# Battery_Monitoring_V3.net
KiCad netlist of a schematic drawn in EAGLE
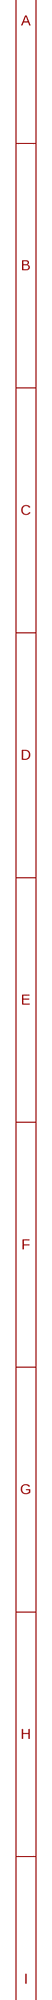
[diagram p0: schematic, sheet 1, part 1 of 2]
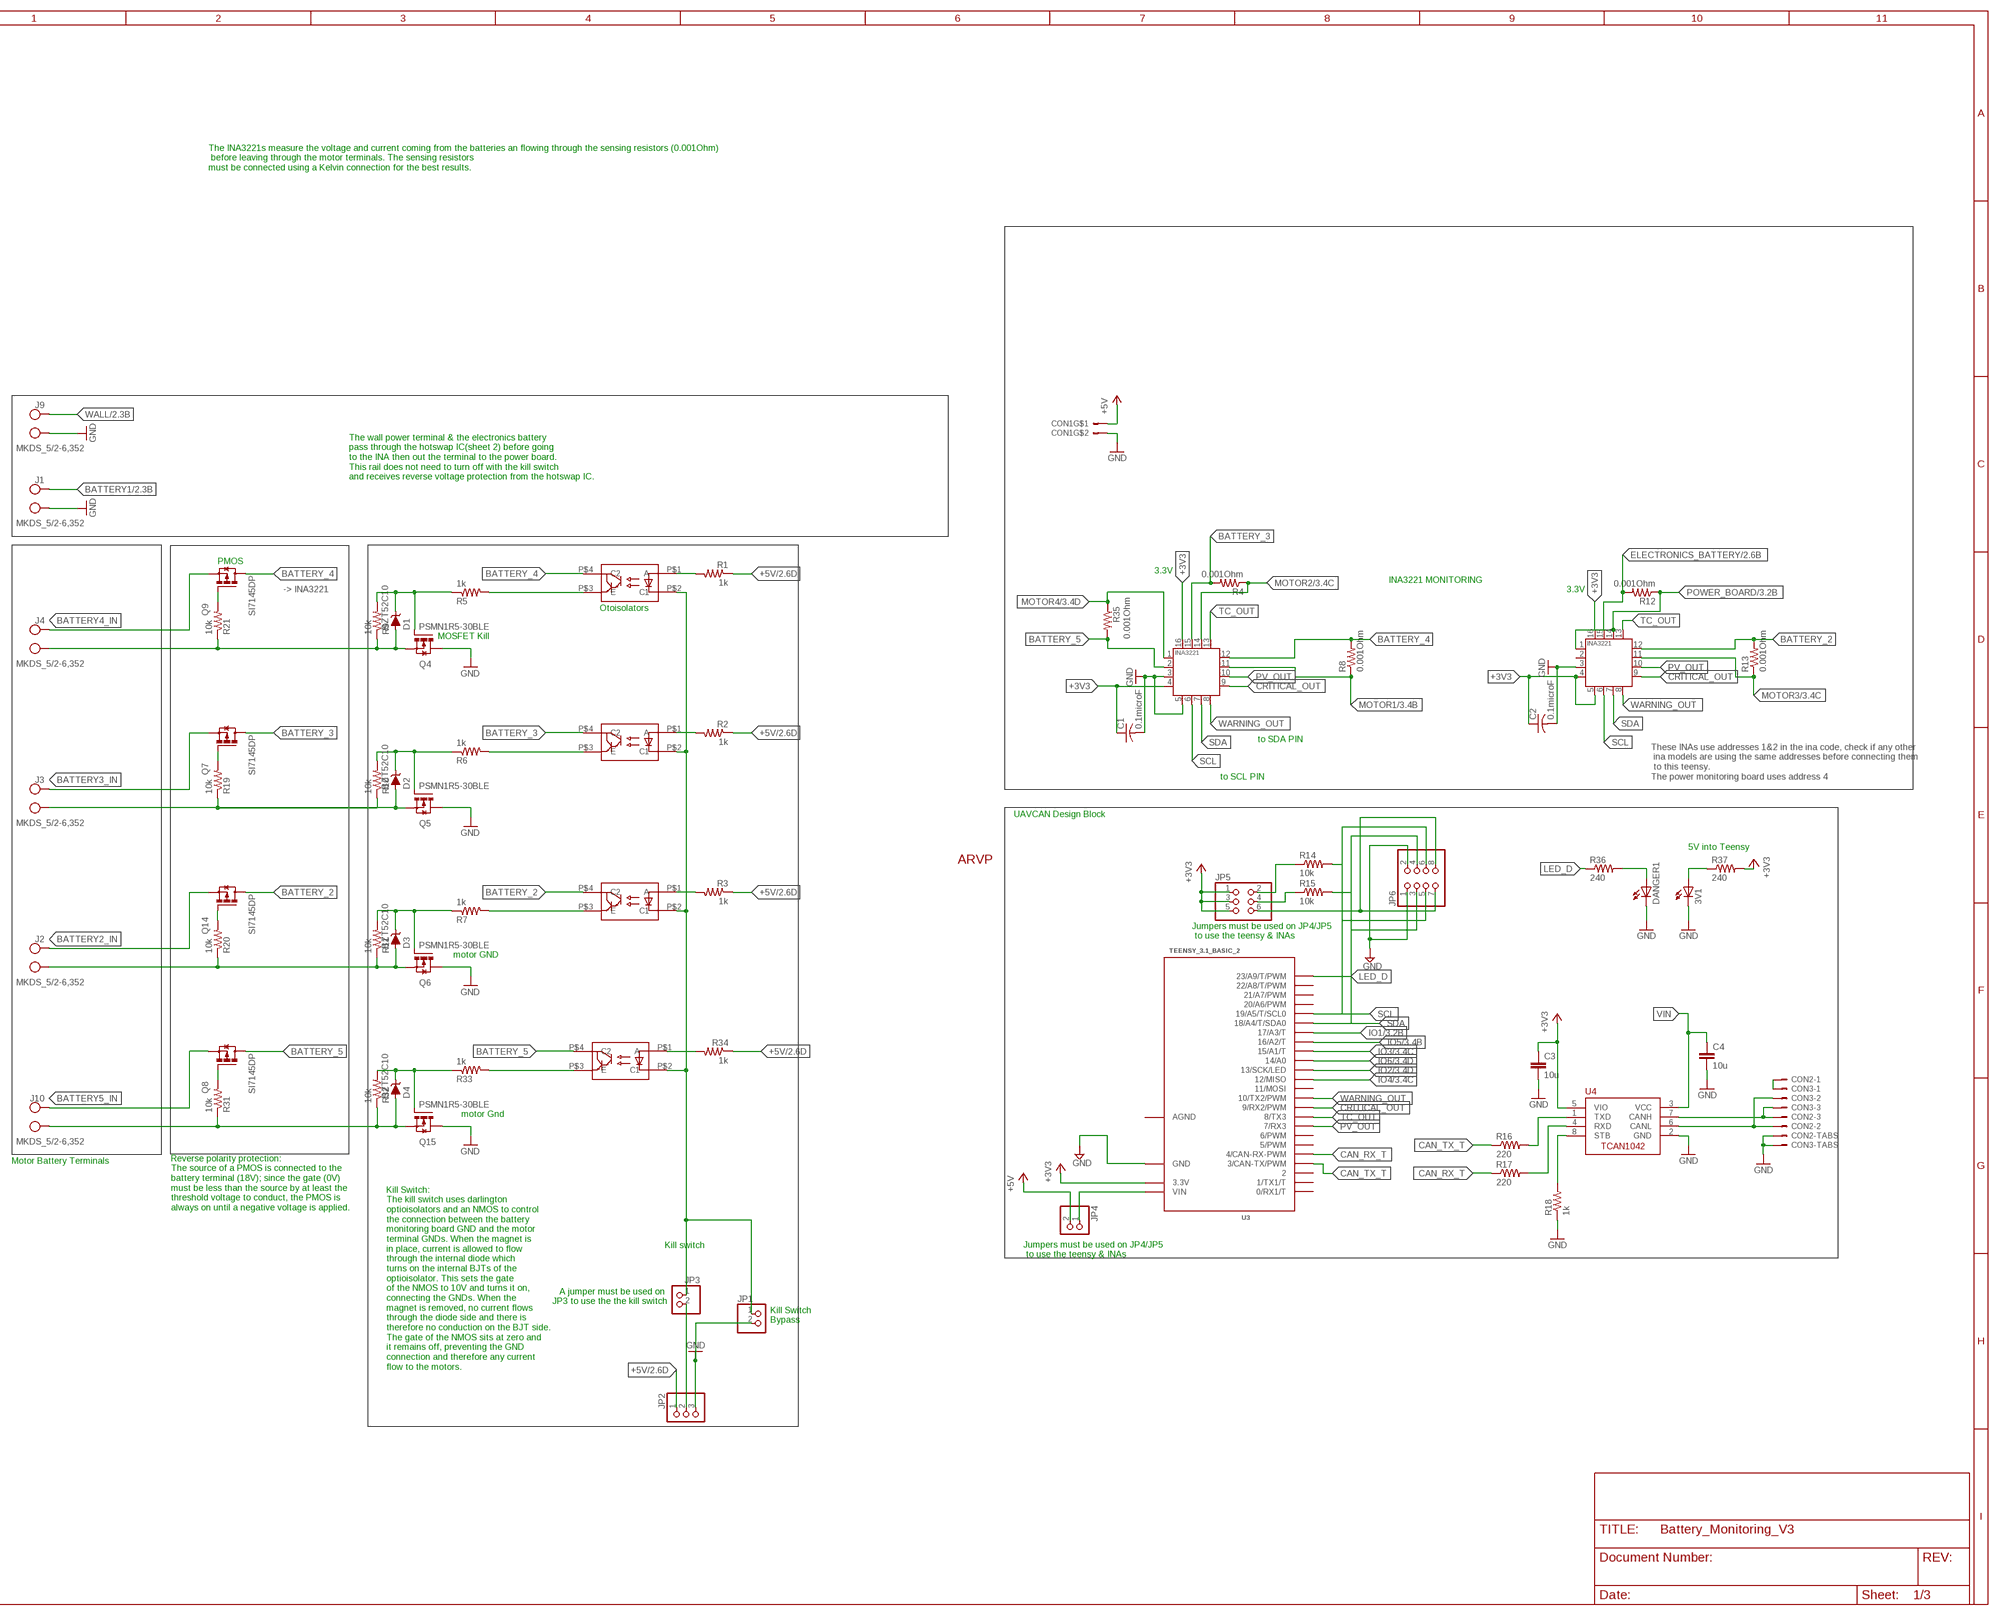
[diagram p1: schematic, sheet 1, part 2 of 2]
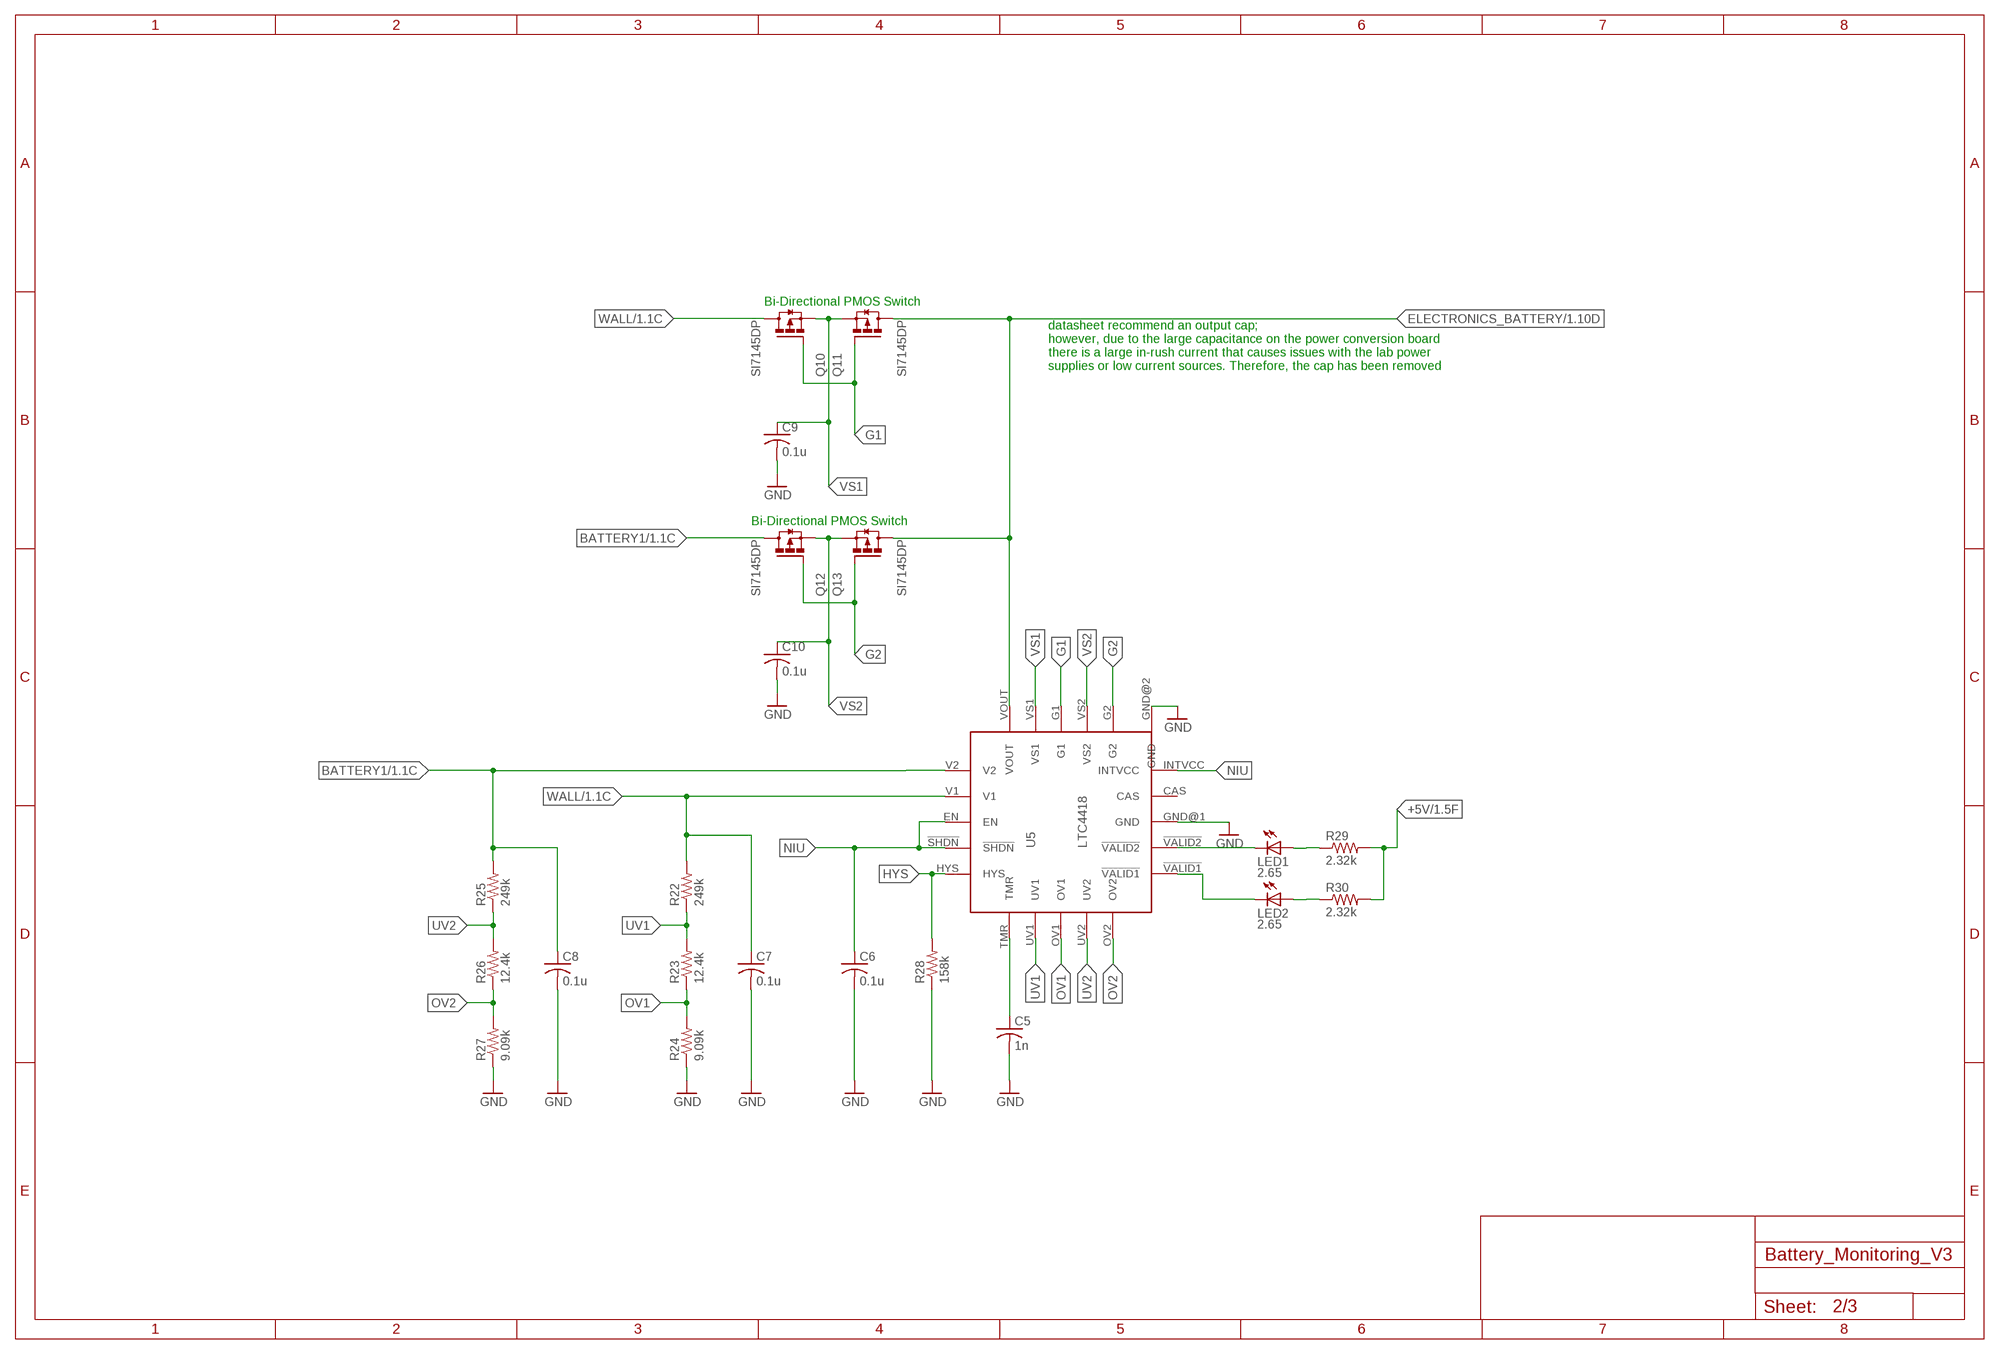
[diagram p2: schematic, sheet 2]
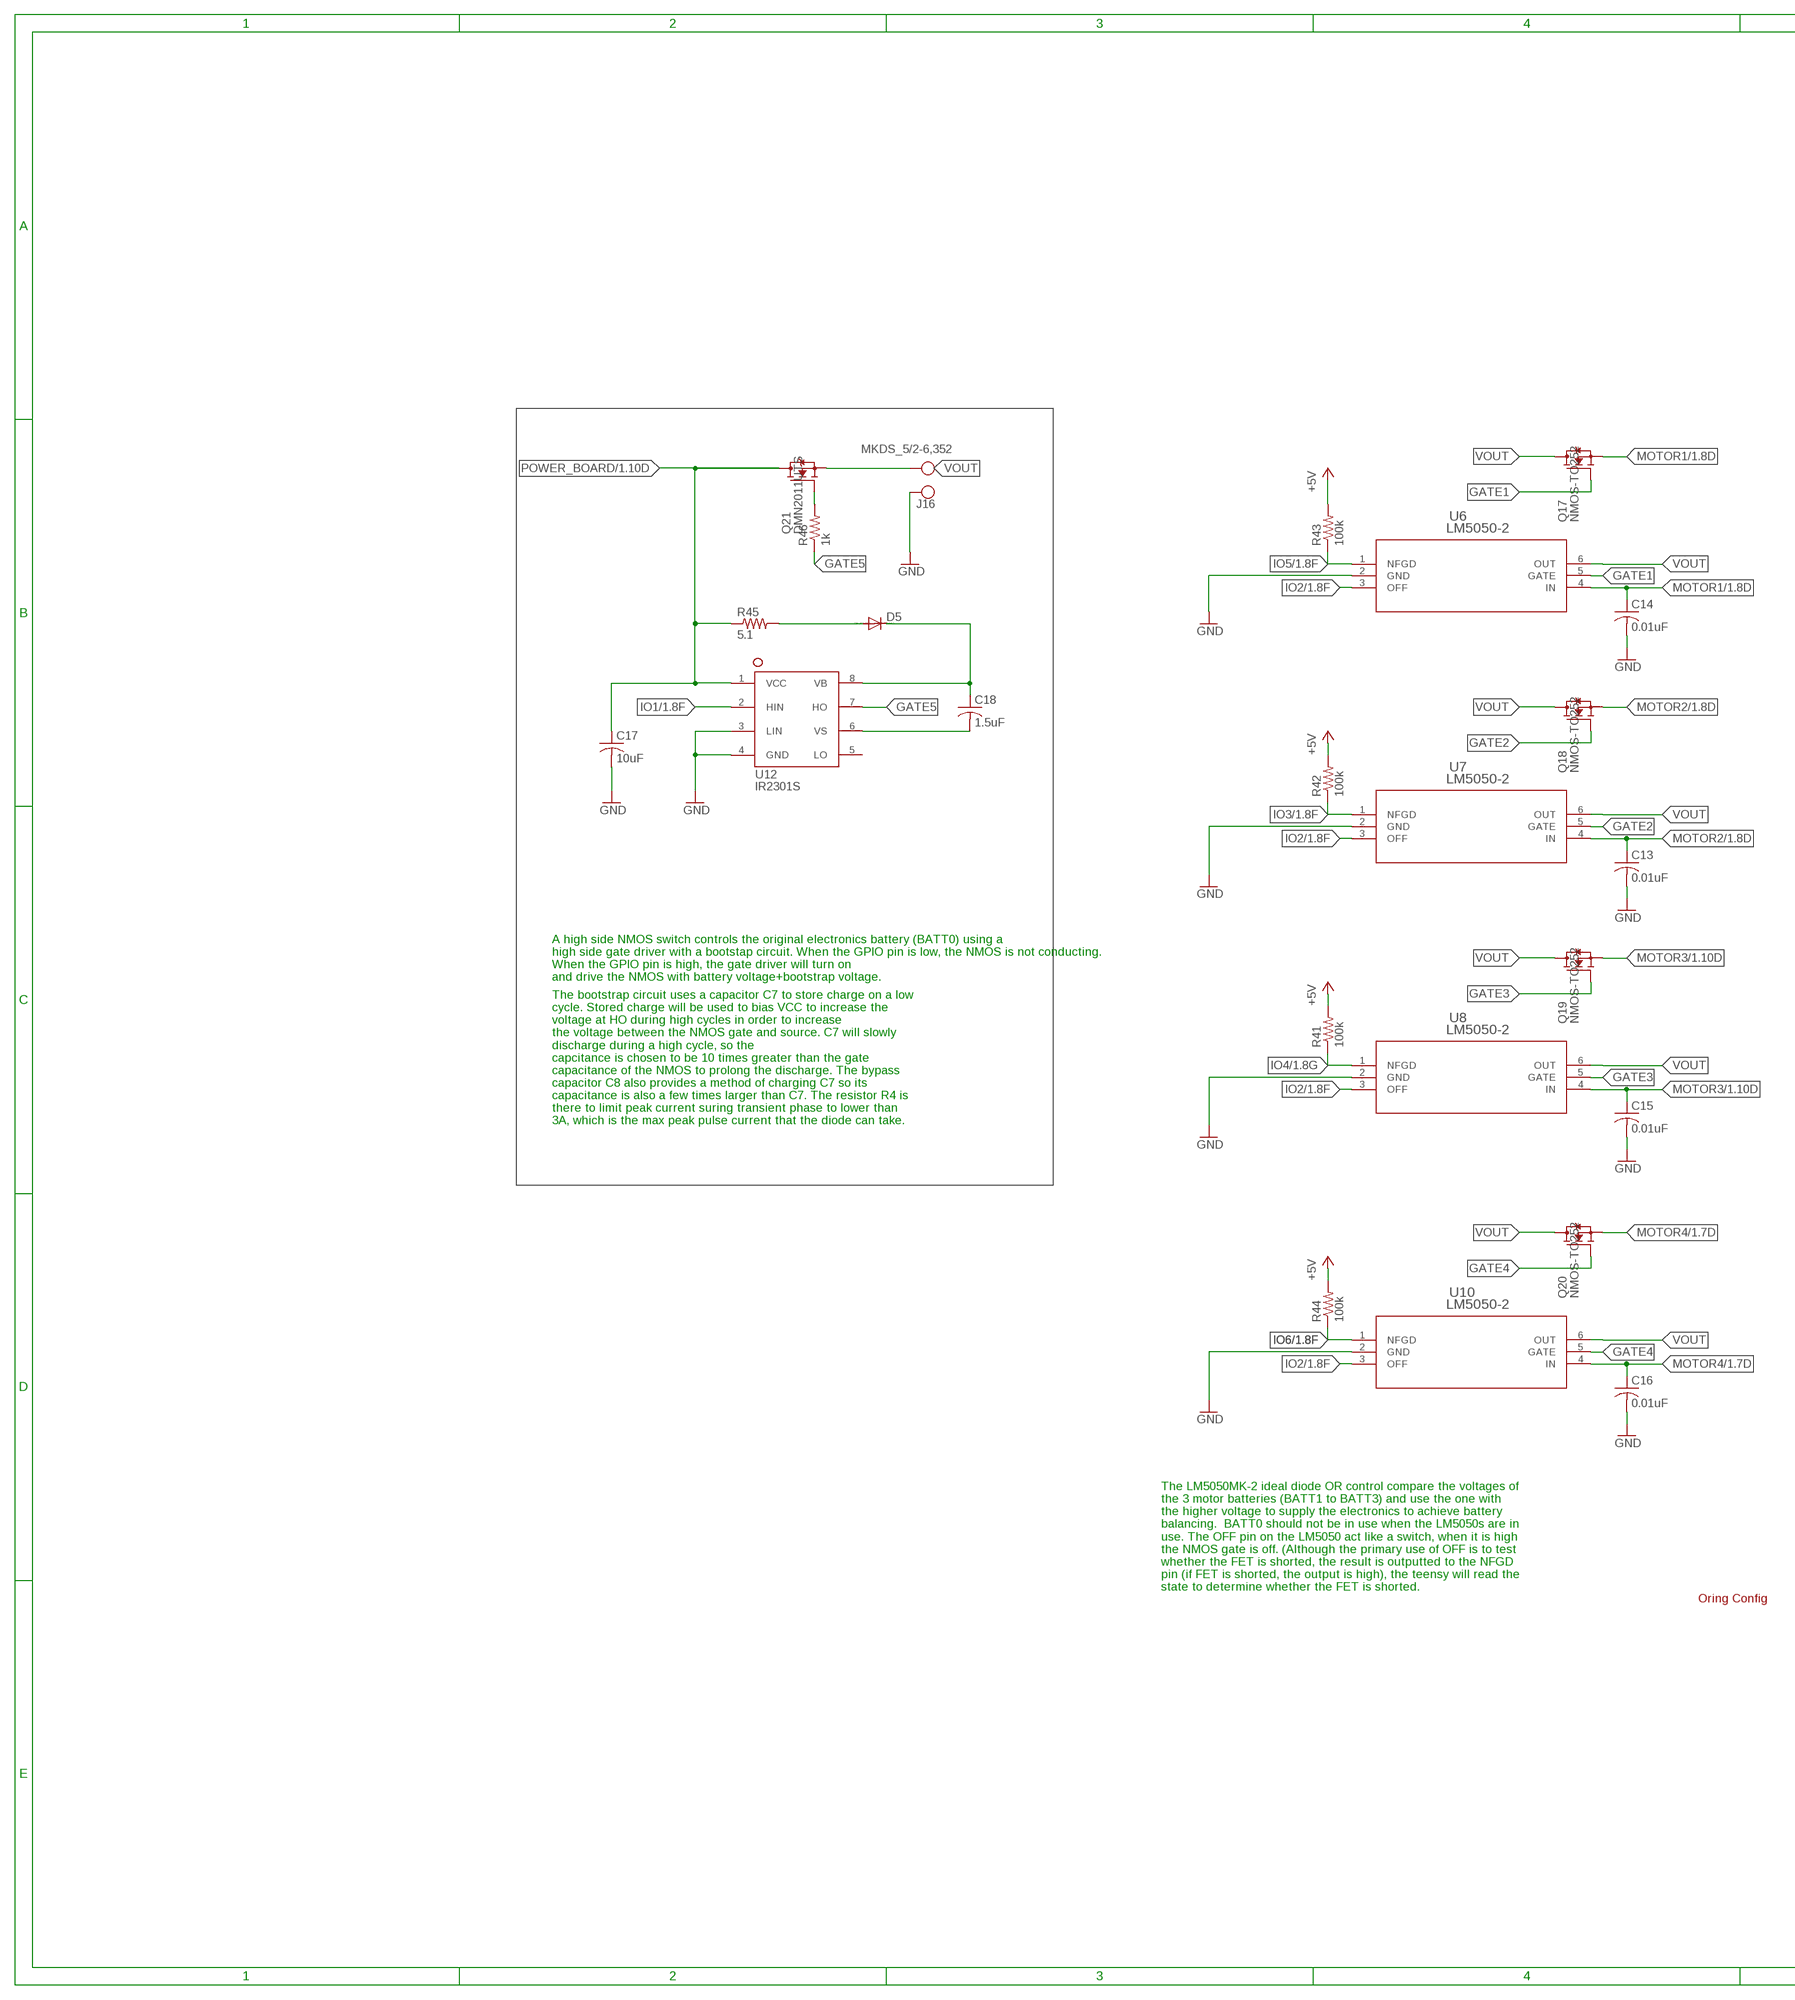
[diagram p3: schematic, sheet 3, part 1 of 2]
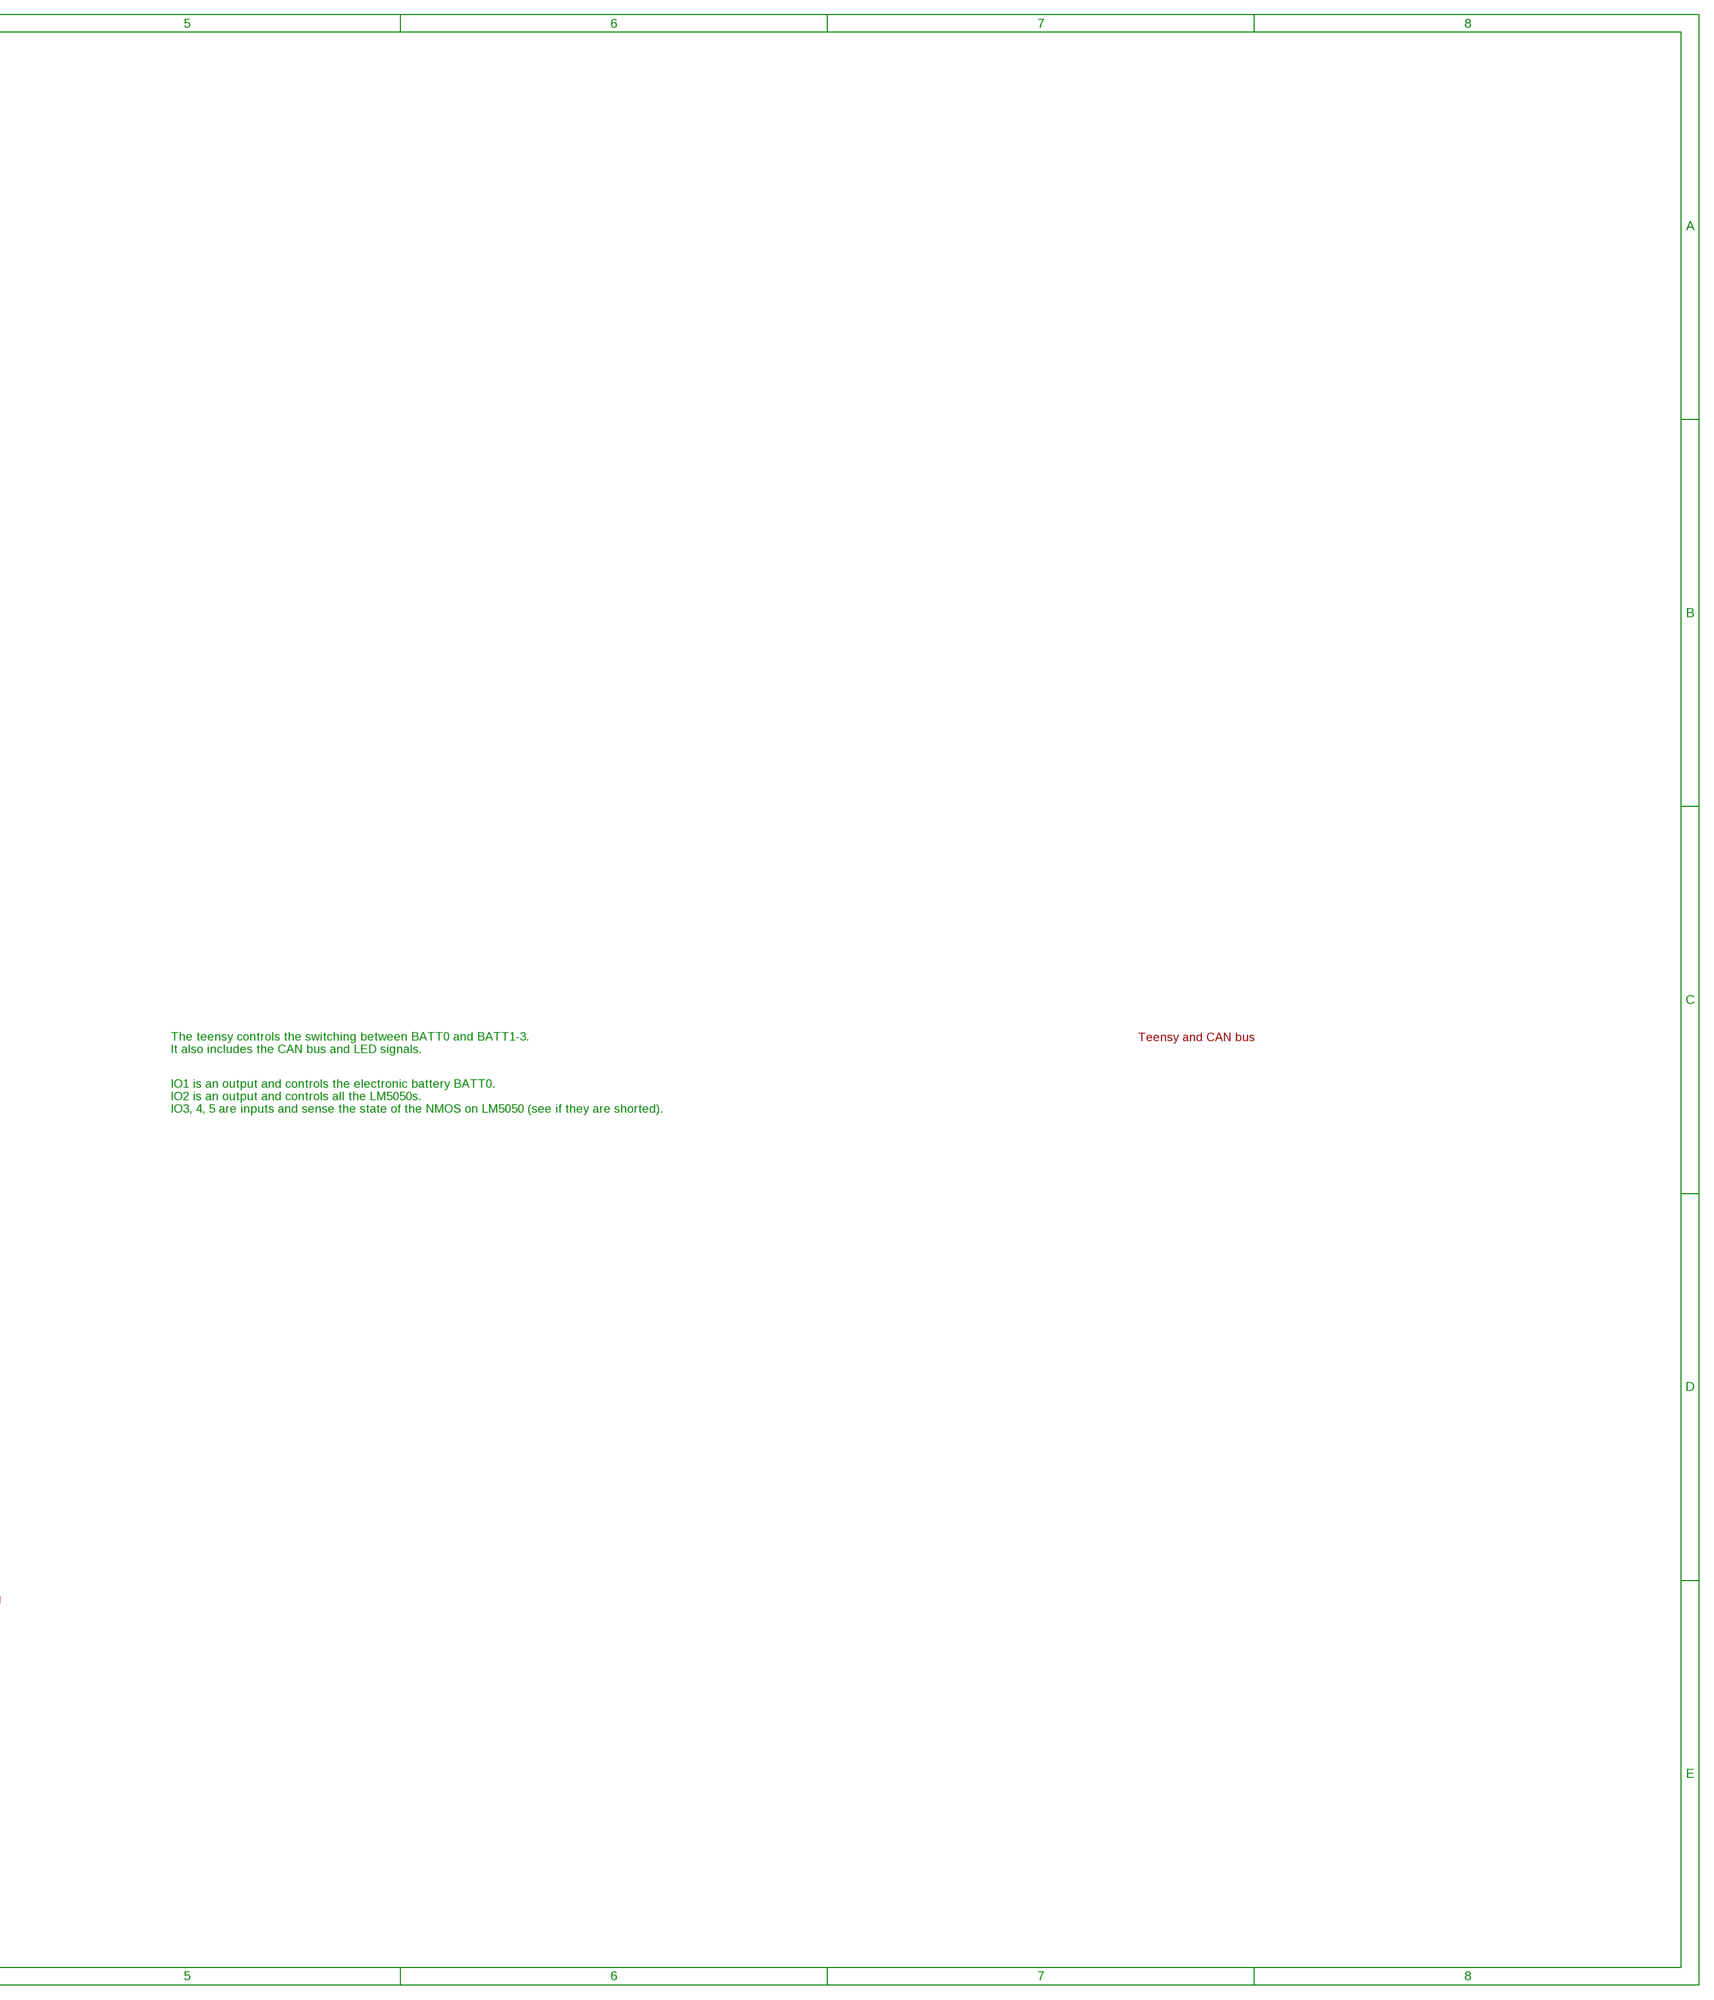
[diagram p4: schematic, sheet 3, part 2 of 2]

(export (version "E")
  (design (tool "Eeschema 10.0.6"))
  (components
    (comp (ref "C13")
      (value "0.01uF")
      (footprint "eagle-import:C0805")
      (libsource (lib "eagle-import") (part "C-USC0805"))
    )
    (comp (ref "C14")
      (value "0.01uF")
      (footprint "eagle-import:C0805")
      (libsource (lib "eagle-import") (part "C-USC0805"))
    )
    (comp (ref "C15")
      (value "0.01uF")
      (footprint "eagle-import:C0805")
      (libsource (lib "eagle-import") (part "C-USC0805"))
    )
    (comp (ref "C16")
      (value "0.01uF")
      (footprint "eagle-import:C0805")
      (libsource (lib "eagle-import") (part "C-USC0805"))
    )
    (comp (ref "C17")
      (value "10uF")
      (footprint "eagle-import:C1206")
      (libsource (lib "eagle-import") (part "C-USC1206"))
    )
    (comp (ref "C18")
      (value "1.5uF")
      (footprint "eagle-import:C0805")
      (libsource (lib "eagle-import") (part "C-USC0805"))
    )
    (comp (ref "D5")
      (value "DIODE-DO-214AC")
      (footprint "eagle-import:DO-214AC")
      (libsource (lib "eagle-import") (part "DIODE-DO-214AC"))
    )
    (comp (ref "J16")
      (value "MKDS_5/2-6,352")
      (footprint "eagle-import:MKDS_5_2-6,35")
      (libsource (lib "eagle-import") (part "MKDS_5/2-6,352"))
    )
    (comp (ref "Q17")
      (value "NMOS-TO252")
      (footprint "eagle-import:TO252")
      (libsource (lib "eagle-import") (part "NMOS-TO252"))
    )
    (comp (ref "Q18")
      (value "NMOS-TO252")
      (footprint "eagle-import:TO252")
      (libsource (lib "eagle-import") (part "NMOS-TO252"))
    )
    (comp (ref "Q19")
      (value "NMOS-TO252")
      (footprint "eagle-import:TO252")
      (libsource (lib "eagle-import") (part "NMOS-TO252"))
    )
    (comp (ref "Q20")
      (value "NMOS-TO252")
      (footprint "eagle-import:TO252")
      (libsource (lib "eagle-import") (part "NMOS-TO252"))
    )
    (comp (ref "Q21")
      (value "DMN2011UTS")
      (footprint "eagle-import:SOP65P640X120-8N")
      (libsource (lib "eagle-import") (part "DMN2011UTS"))
    )
    (comp (ref "R41")
      (value "100k")
      (footprint "eagle-import:R1206")
      (libsource (lib "eagle-import") (part "adafruit_420_R-US_R1206"))
    )
    (comp (ref "R42")
      (value "100k")
      (footprint "eagle-import:R1206")
      (libsource (lib "eagle-import") (part "adafruit_420_R-US_R1206"))
    )
    (comp (ref "R43")
      (value "100k")
      (footprint "eagle-import:R1206")
      (libsource (lib "eagle-import") (part "adafruit_420_R-US_R1206"))
    )
    (comp (ref "R44")
      (value "100k")
      (footprint "eagle-import:R1206")
      (libsource (lib "eagle-import") (part "adafruit_420_R-US_R1206"))
    )
    (comp (ref "R45")
      (value "5.1")
      (footprint "eagle-import:R1206")
      (libsource (lib "eagle-import") (part "adafruit_420_R-US_R1206"))
    )
    (comp (ref "R46")
      (value "1k")
      (footprint "eagle-import:R0805")
      (libsource (lib "eagle-import") (part "rcl_334_R-US_R0805"))
    )
    (comp (ref "U6")
      (value "LM5050-2")
      (footprint "eagle-import:MK06A")
      (libsource (lib "eagle-import") (part "LM5050-2"))
    )
    (comp (ref "U7")
      (value "LM5050-2")
      (footprint "eagle-import:MK06A")
      (libsource (lib "eagle-import") (part "LM5050-2"))
    )
    (comp (ref "U8")
      (value "LM5050-2")
      (footprint "eagle-import:MK06A")
      (libsource (lib "eagle-import") (part "LM5050-2"))
    )
    (comp (ref "U10")
      (value "LM5050-2")
      (footprint "eagle-import:MK06A")
      (libsource (lib "eagle-import") (part "LM5050-2"))
    )
    (comp (ref "U12")
      (value "IR2301S")
      (footprint "eagle-import:SOIC8")
      (libsource (lib "eagle-import") (part "IR2301S"))
    )
    (comp (ref "3V1")
      (value "LEDSMT1206")
      (footprint "eagle-import:1206")
      (libsource (lib "eagle-import") (part "LEDSMT1206"))
    )
    (comp (ref "ARVP1")
      (value "ARVP_LOGO")
      (footprint "eagle-import:ARVP")
      (libsource (lib "eagle-import") (part "ARVP_LOGO"))
    )
    (comp (ref "C1")
      (value "0.1microF")
      (footprint "eagle-import:C2012")
      (libsource (lib "eagle-import") (part "resistor_348_C-USC2012"))
    )
    (comp (ref "C2")
      (value "0.1microF")
      (footprint "eagle-import:C2012")
      (libsource (lib "eagle-import") (part "resistor_348_C-USC2012"))
    )
    (comp (ref "C3")
      (value "10u")
      (footprint "eagle-import:C0805")
      (libsource (lib "eagle-import") (part "C-EUC0805"))
    )
    (comp (ref "C4")
      (value "10u")
      (footprint "eagle-import:C0805")
      (libsource (lib "eagle-import") (part "C-EUC0805"))
    )
    (comp (ref "CON1")
      (value "MOLEX_5566-2")
      (footprint "eagle-import:5566-2")
      (libsource (lib "eagle-import") (part "MOLEX_5566-2"))
    )
    (comp (ref "CON2")
      (value "SM03B-GHS-TB")
      (footprint "eagle-import:SM03B-GHS-TB")
      (libsource (lib "eagle-import") (part "SM03B-GHS-TB"))
    )
    (comp (ref "CON3")
      (value "SM03B-GHS-TB")
      (footprint "eagle-import:SM03B-GHS-TB")
      (libsource (lib "eagle-import") (part "SM03B-GHS-TB"))
    )
    (comp (ref "D1")
      (value "BZT52C10")
      (footprint "eagle-import:SOD-123")
      (libsource (lib "eagle-import") (part "BZT52C10"))
    )
    (comp (ref "D2")
      (value "BZT52C10")
      (footprint "eagle-import:SOD-123")
      (libsource (lib "eagle-import") (part "BZT52C10"))
    )
    (comp (ref "D3")
      (value "BZT52C10")
      (footprint "eagle-import:SOD-123")
      (libsource (lib "eagle-import") (part "BZT52C10"))
    )
    (comp (ref "D4")
      (value "BZT52C10")
      (footprint "eagle-import:SOD-123")
      (libsource (lib "eagle-import") (part "BZT52C10"))
    )
    (comp (ref "DANGER1")
      (value "LEDSMT1206")
      (footprint "eagle-import:1206")
      (libsource (lib "eagle-import") (part "LEDSMT1206"))
    )
    (comp (ref "J1")
      (value "MKDS_5/2-6,352")
      (footprint "eagle-import:MKDS_5_2-6,35")
      (libsource (lib "eagle-import") (part "MKDS_5/2-6,352"))
    )
    (comp (ref "J2")
      (value "MKDS_5/2-6,352")
      (footprint "eagle-import:MKDS_5_2-6,35")
      (libsource (lib "eagle-import") (part "MKDS_5/2-6,352"))
    )
    (comp (ref "J3")
      (value "MKDS_5/2-6,352")
      (footprint "eagle-import:MKDS_5_2-6,35")
      (libsource (lib "eagle-import") (part "MKDS_5/2-6,352"))
    )
    (comp (ref "J4")
      (value "MKDS_5/2-6,352")
      (footprint "eagle-import:MKDS_5_2-6,35")
      (libsource (lib "eagle-import") (part "MKDS_5/2-6,352"))
    )
    (comp (ref "J9")
      (value "MKDS_5/2-6,352")
      (footprint "eagle-import:MKDS_5_2-6,35")
      (libsource (lib "eagle-import") (part "MKDS_5/2-6,352"))
    )
    (comp (ref "J10")
      (value "MKDS_5/2-6,352")
      (footprint "eagle-import:MKDS_5_2-6,35")
      (libsource (lib "eagle-import") (part "MKDS_5/2-6,352"))
    )
    (comp (ref "JP1")
      (value "PINHD-1X2")
      (footprint "eagle-import:1X02")
      (libsource (lib "eagle-import") (part "PINHD-1X2"))
    )
    (comp (ref "JP2")
      (value "PINHD-1X3")
      (footprint "eagle-import:1X03")
      (libsource (lib "eagle-import") (part "PINHD-1X3"))
    )
    (comp (ref "JP3")
      (value "PINHD-1X2")
      (footprint "eagle-import:1X02")
      (libsource (lib "eagle-import") (part "PINHD-1X2"))
    )
    (comp (ref "JP4")
      (value "PINHD-1X2")
      (footprint "eagle-import:1X02")
      (libsource (lib "eagle-import") (part "PINHD-1X2"))
    )
    (comp (ref "JP5")
      (value "PINHD-2X3")
      (footprint "eagle-import:2X03")
      (libsource (lib "eagle-import") (part "PINHD-2X3"))
    )
    (comp (ref "JP6")
      (value "PINHD-2X4")
      (footprint "eagle-import:2X04")
      (libsource (lib "eagle-import") (part "PINHD-2X4"))
    )
    (comp (ref "Q1")
      (value "TCLD1000CT")
      (footprint "eagle-import:SOP-4L")
      (fields (field (name "SPICEPREFIX") "E"))
      (libsource (lib "eagle-import") (part "TCLD1000CT"))
    )
    (comp (ref "Q2")
      (value "TCLD1000CT")
      (footprint "eagle-import:SOP-4L")
      (libsource (lib "eagle-import") (part "TCLD1000CT"))
    )
    (comp (ref "Q3")
      (value "TCLD1000CT")
      (footprint "eagle-import:SOP-4L")
      (libsource (lib "eagle-import") (part "TCLD1000CT"))
    )
    (comp (ref "Q4")
      (value "PSMN1R5-30BLE")
      (footprint "eagle-import:SOT404_D2PAK")
      (libsource (lib "eagle-import") (part "PSMN1R5-30BLE"))
    )
    (comp (ref "Q5")
      (value "PSMN1R5-30BLE")
      (footprint "eagle-import:SOT404_D2PAK")
      (libsource (lib "eagle-import") (part "PSMN1R5-30BLE"))
    )
    (comp (ref "Q6")
      (value "PSMN1R5-30BLE")
      (footprint "eagle-import:SOT404_D2PAK")
      (libsource (lib "eagle-import") (part "PSMN1R5-30BLE"))
    )
    (comp (ref "Q7")
      (value "SI7145DP")
      (footprint "eagle-import:SO-8_PPAK_TEST")
      (fields (field (name "MPN") "SI7145DP-T1-GE3"))
      (libsource (lib "eagle-import") (part "Si7145DP_SI7145DP"))
    )
    (comp (ref "Q8")
      (value "SI7145DP")
      (footprint "eagle-import:SO-8_PPAK_TEST")
      (fields (field (name "MPN") "SI7145DP-T1-GE3"))
      (libsource (lib "eagle-import") (part "Si7145DP_SI7145DP"))
    )
    (comp (ref "Q9")
      (value "SI7145DP")
      (footprint "eagle-import:SO-8_PPAK_TEST")
      (fields (field (name "MPN") "SI7145DP-T1-GE3"))
      (libsource (lib "eagle-import") (part "Si7145DP_SI7145DP"))
    )
    (comp (ref "Q14")
      (value "SI7145DP")
      (footprint "eagle-import:SO-8_PPAK_TEST")
      (fields (field (name "MPN") "SI7145DP-T1-GE3"))
      (libsource (lib "eagle-import") (part "Si7145DP_SI7145DP"))
    )
    (comp (ref "Q15")
      (value "PSMN1R5-30BLE")
      (footprint "eagle-import:SOT404_D2PAK")
      (libsource (lib "eagle-import") (part "PSMN1R5-30BLE"))
    )
    (comp (ref "Q16")
      (value "TCLD1000CT")
      (footprint "eagle-import:SOP-4L")
      (libsource (lib "eagle-import") (part "TCLD1000CT"))
    )
    (comp (ref "R1")
      (value "1k")
      (footprint "eagle-import:R0805")
      (libsource (lib "eagle-import") (part "adafruit_420_R-US_R0805"))
    )
    (comp (ref "R2")
      (value "1k")
      (footprint "eagle-import:R0805")
      (libsource (lib "eagle-import") (part "adafruit_420_R-US_R0805"))
    )
    (comp (ref "R3")
      (value "1k")
      (footprint "eagle-import:R0805")
      (libsource (lib "eagle-import") (part "adafruit_420_R-US_R0805"))
    )
    (comp (ref "R4")
      (value "0.001Ohm")
      (footprint "eagle-import:3920")
      (libsource (lib "eagle-import") (part "HCS3920FT1L00"))
    )
    (comp (ref "R5")
      (value "1k")
      (footprint "eagle-import:M1206")
      (libsource (lib "eagle-import") (part "adafruit_420_R-US_M1206"))
    )
    (comp (ref "R6")
      (value "1k")
      (footprint "eagle-import:M1206")
      (libsource (lib "eagle-import") (part "adafruit_420_R-US_M1206"))
    )
    (comp (ref "R7")
      (value "1k")
      (footprint "eagle-import:M1206")
      (libsource (lib "eagle-import") (part "adafruit_420_R-US_M1206"))
    )
    (comp (ref "R8")
      (value "0.001Ohm")
      (footprint "eagle-import:3920")
      (libsource (lib "eagle-import") (part "HCS3920FT1L00"))
    )
    (comp (ref "R9")
      (value "10k")
      (footprint "eagle-import:M1206")
      (libsource (lib "eagle-import") (part "adafruit_420_R-US_M1206"))
    )
    (comp (ref "R10")
      (value "10k")
      (footprint "eagle-import:M1206")
      (libsource (lib "eagle-import") (part "adafruit_420_R-US_M1206"))
    )
    (comp (ref "R11")
      (value "10k")
      (footprint "eagle-import:M1206")
      (libsource (lib "eagle-import") (part "adafruit_420_R-US_M1206"))
    )
    (comp (ref "R12")
      (value "0.001Ohm")
      (footprint "eagle-import:3920")
      (libsource (lib "eagle-import") (part "HCS3920FT1L00"))
    )
    (comp (ref "R13")
      (value "0.001Ohm")
      (footprint "eagle-import:3920")
      (libsource (lib "eagle-import") (part "HCS3920FT1L00"))
    )
    (comp (ref "R14")
      (value "10k")
      (footprint "eagle-import:R1206")
      (libsource (lib "eagle-import") (part "rcl_334_R-US_R1206"))
    )
    (comp (ref "R15")
      (value "10k")
      (footprint "eagle-import:R1206")
      (libsource (lib "eagle-import") (part "rcl_334_R-US_R1206"))
    )
    (comp (ref "R16")
      (value "220")
      (footprint "eagle-import:R0805")
      (libsource (lib "eagle-import") (part "rcl_334_R-US_R0805"))
    )
    (comp (ref "R17")
      (value "220")
      (footprint "eagle-import:R0805")
      (libsource (lib "eagle-import") (part "rcl_334_R-US_R0805"))
    )
    (comp (ref "R18")
      (value "1k")
      (footprint "eagle-import:R0805")
      (libsource (lib "eagle-import") (part "rcl_334_R-US_R0805"))
    )
    (comp (ref "R19")
      (value "10k")
      (footprint "eagle-import:M1206")
      (fields (field (name "MPN") "RC0603FR-0710KL"))
      (libsource (lib "eagle-import") (part "R-US_M1206"))
    )
    (comp (ref "R20")
      (value "10k")
      (footprint "eagle-import:M1206")
      (fields (field (name "MPN") "RC0603FR-0710KL"))
      (libsource (lib "eagle-import") (part "R-US_M1206"))
    )
    (comp (ref "R21")
      (value "10k")
      (footprint "eagle-import:M1206")
      (fields (field (name "MPN") "RC0603FR-0710KL"))
      (libsource (lib "eagle-import") (part "adafruit_420_R-US_M1206"))
    )
    (comp (ref "R31")
      (value "10k")
      (footprint "eagle-import:M1206")
      (fields (field (name "MPN") "RC0603FR-0710KL"))
      (libsource (lib "eagle-import") (part "R-US_M1206"))
    )
    (comp (ref "R32")
      (value "10k")
      (footprint "eagle-import:M1206")
      (libsource (lib "eagle-import") (part "adafruit_420_R-US_M1206"))
    )
    (comp (ref "R33")
      (value "1k")
      (footprint "eagle-import:M1206")
      (libsource (lib "eagle-import") (part "adafruit_420_R-US_M1206"))
    )
    (comp (ref "R34")
      (value "1k")
      (footprint "eagle-import:R0805")
      (libsource (lib "eagle-import") (part "adafruit_420_R-US_R0805"))
    )
    (comp (ref "R35")
      (value "0.001Ohm")
      (footprint "eagle-import:3920")
      (libsource (lib "eagle-import") (part "HCS3920FT1L00"))
    )
    (comp (ref "R36")
      (value "240")
      (footprint "eagle-import:R1206")
      (libsource (lib "eagle-import") (part "resistor_348_R-US_R1206"))
    )
    (comp (ref "R37")
      (value "240")
      (footprint "eagle-import:R1206")
      (libsource (lib "eagle-import") (part "resistor_348_R-US_R1206"))
    )
    (comp (ref "U1")
      (value "INA3221.")
      (footprint "eagle-import:HVQFN16_4X4")
      (libsource (lib "eagle-import") (part "INA3221."))
    )
    (comp (ref "U2")
      (value "INA3221.")
      (footprint "eagle-import:HVQFN16_4X4")
      (libsource (lib "eagle-import") (part "INA3221."))
    )
    (comp (ref "U3")
      (value "TEENSY_3.1_BASIC_2")
      (footprint "eagle-import:TEENSY_3.1_BASIC_2")
      (libsource (lib "eagle-import") (part "TEENSY_3.1_BASIC_2"))
    )
    (comp (ref "U4")
      (value "TCAN1042HVDR")
      (footprint "eagle-import:SO-8")
      (libsource (lib "eagle-import") (part "TCAN1042HVDR"))
    )
    (comp (ref "C5")
      (value "1n")
      (footprint "eagle-import:C0805")
      (libsource (lib "eagle-import") (part "C-USC0805"))
    )
    (comp (ref "C6")
      (value "0.1u")
      (footprint "eagle-import:C0805")
      (libsource (lib "eagle-import") (part "C-USC0805"))
    )
    (comp (ref "C7")
      (value "0.1u")
      (footprint "eagle-import:C0805")
      (libsource (lib "eagle-import") (part "C-USC0805"))
    )
    (comp (ref "C8")
      (value "0.1u")
      (footprint "eagle-import:C0805")
      (libsource (lib "eagle-import") (part "C-USC0805"))
    )
    (comp (ref "C9")
      (value "0.1u")
      (footprint "eagle-import:C0805")
      (libsource (lib "eagle-import") (part "C-USC0805"))
    )
    (comp (ref "C10")
      (value "0.1u")
      (footprint "eagle-import:C0805")
      (libsource (lib "eagle-import") (part "C-USC0805"))
    )
    (comp (ref "LED1")
      (value "2.65")
      (footprint "eagle-import:SML0805")
      (libsource (lib "eagle-import") (part "LEDSML0805"))
    )
    (comp (ref "LED2")
      (value "2.65")
      (footprint "eagle-import:SML0805")
      (libsource (lib "eagle-import") (part "LEDSML0805"))
    )
    (comp (ref "Q10")
      (value "SI7145DP")
      (footprint "eagle-import:SO-8_PPAK_TEST")
      (libsource (lib "eagle-import") (part "SI7145DP"))
    )
    (comp (ref "Q11")
      (value "SI7145DP")
      (footprint "eagle-import:SO-8_PPAK_TEST")
      (libsource (lib "eagle-import") (part "SI7145DP"))
    )
    (comp (ref "Q12")
      (value "SI7145DP")
      (footprint "eagle-import:SO-8_PPAK_TEST")
      (libsource (lib "eagle-import") (part "SI7145DP"))
    )
    (comp (ref "Q13")
      (value "SI7145DP")
      (footprint "eagle-import:SO-8_PPAK_TEST")
      (libsource (lib "eagle-import") (part "SI7145DP"))
    )
    (comp (ref "R22")
      (value "249k")
      (footprint "eagle-import:R1206")
      (libsource (lib "eagle-import") (part "adafruit_420_R-US_R1206"))
    )
    (comp (ref "R23")
      (value "12.4k")
      (footprint "eagle-import:R0805")
      (libsource (lib "eagle-import") (part "adafruit_420_R-US_R0805"))
    )
    (comp (ref "R24")
      (value "9.09k")
      (footprint "eagle-import:R0805")
      (libsource (lib "eagle-import") (part "adafruit_420_R-US_R0805"))
    )
    (comp (ref "R25")
      (value "249k")
      (footprint "eagle-import:R1206")
      (libsource (lib "eagle-import") (part "adafruit_420_R-US_R1206"))
    )
    (comp (ref "R26")
      (value "12.4k")
      (footprint "eagle-import:R0805")
      (libsource (lib "eagle-import") (part "adafruit_420_R-US_R0805"))
    )
    (comp (ref "R27")
      (value "9.09k")
      (footprint "eagle-import:R0805")
      (libsource (lib "eagle-import") (part "adafruit_420_R-US_R0805"))
    )
    (comp (ref "R28")
      (value "158k")
      (footprint "eagle-import:R0805")
      (libsource (lib "eagle-import") (part "adafruit_420_R-US_R0805"))
    )
    (comp (ref "R29")
      (value "2.32k")
      (footprint "eagle-import:R0805")
      (libsource (lib "eagle-import") (part "adafruit_420_R-US_R0805"))
    )
    (comp (ref "R30")
      (value "2.32k")
      (footprint "eagle-import:R0805")
      (libsource (lib "eagle-import") (part "adafruit_420_R-US_R0805"))
    )
    (comp (ref "U5")
      (value "LTC4418")
      (footprint "eagle-import:20-QFN(4X4)")
      (libsource (lib "eagle-import") (part "LTC4418"))
    )
  )
  (nets
    (net (code "1") (name "+3V3") (class "Default")
      (node (ref "C1") (pin "1") (pinfunction "1_1") (pintype "passive"))
      (node (ref "C2") (pin "1") (pinfunction "1_1") (pintype "passive"))
      (node (ref "C3") (pin "1") (pinfunction "1_1") (pintype "passive"))
      (node (ref "JP5") (pin "1") (pinfunction "1_1") (pintype "passive"))
      (node (ref "JP5") (pin "3") (pinfunction "3_3") (pintype "passive"))
      (node (ref "JP5") (pin "5") (pinfunction "5_5") (pintype "passive"))
      (node (ref "R37") (pin "2") (pinfunction "2_2") (pintype "passive"))
      (node (ref "U1") (pin "16") (pinfunction "VPU_16") (pintype "input"))
      (node (ref "U1") (pin "4") (pinfunction "VS_4") (pintype "power_in"))
      (node (ref "U2") (pin "16") (pinfunction "VPU_16") (pintype "input"))
      (node (ref "U2") (pin "4") (pinfunction "VS_4") (pintype "power_in"))
      (node (ref "U2") (pin "5") (pinfunction "A0_5") (pintype "input"))
      (node (ref "U3") (pin "3.3V") (pinfunction "3.3V_3.3V") (pintype "power_in"))
      (node (ref "U4") (pin "5") (pinfunction "VIO_5") (pintype "bidirectional"))
    )
    (net (code "2") (name "+5V") (class "Default")
      (node (ref "CON1") (pin "1") (pinfunction "S_1") (pintype "passive"))
      (node (ref "JP2") (pin "1") (pinfunction "1_1") (pintype "passive"))
      (node (ref "JP4") (pin "2") (pinfunction "2_2") (pintype "passive"))
      (node (ref "R1") (pin "1") (pinfunction "1_1") (pintype "passive"))
      (node (ref "R2") (pin "1") (pinfunction "1_1") (pintype "passive"))
      (node (ref "R29") (pin "2") (pinfunction "2_2") (pintype "passive"))
      (node (ref "R3") (pin "1") (pinfunction "1_1") (pintype "passive"))
      (node (ref "R30") (pin "2") (pinfunction "2_2") (pintype "passive"))
      (node (ref "R34") (pin "1") (pinfunction "1_1") (pintype "passive"))
      (node (ref "R41") (pin "2") (pinfunction "2_2") (pintype "passive"))
      (node (ref "R42") (pin "2") (pinfunction "2_2") (pintype "passive"))
      (node (ref "R43") (pin "2") (pinfunction "2_2") (pintype "passive"))
      (node (ref "R44") (pin "2") (pinfunction "2_2") (pintype "passive"))
    )
    (net (code "3") (name "AGND") (class "Default")
      (node (ref "U3") (pin "AGND") (pinfunction "AGND_AGND") (pintype "power_in"))
    )
    (net (code "4") (name "BATTERY1") (class "Default")
      (node (ref "C8") (pin "1") (pinfunction "1_1") (pintype "passive"))
      (node (ref "J1") (pin "2") (pinfunction "KL1_2") (pintype "passive"))
      (node (ref "Q12") (pin "D@1") (pinfunction "D_D@1") (pintype "passive"))
      (node (ref "Q12") (pin "D@2") (pinfunction "D_D@2") (pintype "passive"))
      (node (ref "Q12") (pin "D@3") (pinfunction "D_D@3") (pintype "passive"))
      (node (ref "Q12") (pin "D@4") (pinfunction "D_D@4") (pintype "passive"))
      (node (ref "Q12") (pin "D@5") (pinfunction "D_D@5") (pintype "passive"))
      (node (ref "R25") (pin "2") (pinfunction "2_2") (pintype "passive"))
      (node (ref "U5") (pin "V2") (pinfunction "V2_V2") (pintype "bidirectional"))
    )
    (net (code "5") (name "BATTERY2_IN") (class "Default")
      (node (ref "J2") (pin "2") (pinfunction "KL1_2") (pintype "passive"))
      (node (ref "Q14") (pin "S@1") (pinfunction "S_S@1") (pintype "passive"))
      (node (ref "Q14") (pin "S@2") (pinfunction "S_S@2") (pintype "passive"))
      (node (ref "Q14") (pin "S@3") (pinfunction "S_S@3") (pintype "passive"))
    )
    (net (code "6") (name "BATTERY3_IN") (class "Default")
      (node (ref "J3") (pin "2") (pinfunction "KL1_2") (pintype "passive"))
      (node (ref "Q7") (pin "S@1") (pinfunction "S_S@1") (pintype "passive"))
      (node (ref "Q7") (pin "S@2") (pinfunction "S_S@2") (pintype "passive"))
      (node (ref "Q7") (pin "S@3") (pinfunction "S_S@3") (pintype "passive"))
    )
    (net (code "7") (name "BATTERY4_IN") (class "Default")
      (node (ref "J4") (pin "2") (pinfunction "KL1_2") (pintype "passive"))
      (node (ref "Q9") (pin "S@1") (pinfunction "S_S@1") (pintype "passive"))
      (node (ref "Q9") (pin "S@2") (pinfunction "S_S@2") (pintype "passive"))
      (node (ref "Q9") (pin "S@3") (pinfunction "S_S@3") (pintype "passive"))
    )
    (net (code "8") (name "BATTERY5_IN") (class "Default")
      (node (ref "J10") (pin "2") (pinfunction "KL1_2") (pintype "passive"))
      (node (ref "Q8") (pin "S@1") (pinfunction "S_S@1") (pintype "passive"))
      (node (ref "Q8") (pin "S@2") (pinfunction "S_S@2") (pintype "passive"))
      (node (ref "Q8") (pin "S@3") (pinfunction "S_S@3") (pintype "passive"))
    )
    (net (code "9") (name "BATTERY_2") (class "Default")
      (node (ref "Q14") (pin "D@1") (pinfunction "D_D@1") (pintype "passive"))
      (node (ref "Q14") (pin "D@2") (pinfunction "D_D@2") (pintype "passive"))
      (node (ref "Q14") (pin "D@3") (pinfunction "D_D@3") (pintype "passive"))
      (node (ref "Q14") (pin "D@4") (pinfunction "D_D@4") (pintype "passive"))
      (node (ref "Q14") (pin "D@5") (pinfunction "D_D@5") (pintype "passive"))
      (node (ref "Q3") (pin "P$4") (pinfunction "C2_P$4") (pintype "bidirectional"))
      (node (ref "R13") (pin "P$2") (pinfunction "2_P$2") (pintype "passive"))
      (node (ref "U2") (pin "12") (pinfunction "IN+1_12") (pintype "input"))
    )
    (net (code "10") (name "BATTERY_3") (class "Default")
      (node (ref "Q2") (pin "P$4") (pinfunction "C2_P$4") (pintype "bidirectional"))
      (node (ref "Q7") (pin "D@1") (pinfunction "D_D@1") (pintype "passive"))
      (node (ref "Q7") (pin "D@2") (pinfunction "D_D@2") (pintype "passive"))
      (node (ref "Q7") (pin "D@3") (pinfunction "D_D@3") (pintype "passive"))
      (node (ref "Q7") (pin "D@4") (pinfunction "D_D@4") (pintype "passive"))
      (node (ref "Q7") (pin "D@5") (pinfunction "D_D@5") (pintype "passive"))
      (node (ref "R4") (pin "P$2") (pinfunction "2_P$2") (pintype "passive"))
      (node (ref "U1") (pin "15") (pinfunction "IN+2_15") (pintype "input"))
    )
    (net (code "11") (name "BATTERY_4") (class "Default")
      (node (ref "Q1") (pin "P$4") (pinfunction "C2_P$4") (pintype "bidirectional"))
      (node (ref "Q9") (pin "D@1") (pinfunction "D_D@1") (pintype "passive"))
      (node (ref "Q9") (pin "D@2") (pinfunction "D_D@2") (pintype "passive"))
      (node (ref "Q9") (pin "D@3") (pinfunction "D_D@3") (pintype "passive"))
      (node (ref "Q9") (pin "D@4") (pinfunction "D_D@4") (pintype "passive"))
      (node (ref "Q9") (pin "D@5") (pinfunction "D_D@5") (pintype "passive"))
      (node (ref "R8") (pin "P$2") (pinfunction "2_P$2") (pintype "passive"))
      (node (ref "U1") (pin "12") (pinfunction "IN+1_12") (pintype "input"))
    )
    (net (code "12") (name "BATTERY_5") (class "Default")
      (node (ref "Q16") (pin "P$4") (pinfunction "C2_P$4") (pintype "bidirectional"))
      (node (ref "Q8") (pin "D@1") (pinfunction "D_D@1") (pintype "passive"))
      (node (ref "Q8") (pin "D@2") (pinfunction "D_D@2") (pintype "passive"))
      (node (ref "Q8") (pin "D@3") (pinfunction "D_D@3") (pintype "passive"))
      (node (ref "Q8") (pin "D@4") (pinfunction "D_D@4") (pintype "passive"))
      (node (ref "Q8") (pin "D@5") (pinfunction "D_D@5") (pintype "passive"))
      (node (ref "R35") (pin "P$2") (pinfunction "2_P$2") (pintype "passive"))
      (node (ref "U1") (pin "2") (pinfunction "IN+3_2") (pintype "input"))
    )
    (net (code "13") (name "CAN_RX_T") (class "Default")
      (node (ref "R17") (pin "1") (pinfunction "1_1") (pintype "passive"))
      (node (ref "U3") (pin "4") (pinfunction "4/CAN-RX-PWM_4") (pintype "bidirectional"))
    )
    (net (code "14") (name "CAN_TX_T") (class "Default")
      (node (ref "R16") (pin "1") (pinfunction "1_1") (pintype "passive"))
      (node (ref "U3") (pin "3") (pinfunction "3/CAN-TX/PWM_3") (pintype "bidirectional"))
    )
    (net (code "15") (name "CRITICAL_OUT") (class "Default")
      (node (ref "U1") (pin "9") (pinfunction "CRITICAL_9") (pintype "output"))
      (node (ref "U2") (pin "9") (pinfunction "CRITICAL_9") (pintype "output"))
      (node (ref "U3") (pin "9") (pinfunction "9/RX2/PWM_9") (pintype "bidirectional"))
    )
    (net (code "16") (name "ELECTRONICS_BATTERY") (class "Default")
      (node (ref "Q11") (pin "D@1") (pinfunction "D_D@1") (pintype "passive"))
      (node (ref "Q11") (pin "D@2") (pinfunction "D_D@2") (pintype "passive"))
      (node (ref "Q11") (pin "D@3") (pinfunction "D_D@3") (pintype "passive"))
      (node (ref "Q11") (pin "D@4") (pinfunction "D_D@4") (pintype "passive"))
      (node (ref "Q11") (pin "D@5") (pinfunction "D_D@5") (pintype "passive"))
      (node (ref "Q13") (pin "D@1") (pinfunction "D_D@1") (pintype "passive"))
      (node (ref "Q13") (pin "D@2") (pinfunction "D_D@2") (pintype "passive"))
      (node (ref "Q13") (pin "D@3") (pinfunction "D_D@3") (pintype "passive"))
      (node (ref "Q13") (pin "D@4") (pinfunction "D_D@4") (pintype "passive"))
      (node (ref "Q13") (pin "D@5") (pinfunction "D_D@5") (pintype "passive"))
      (node (ref "R12") (pin "P$2") (pinfunction "2_P$2") (pintype "passive"))
      (node (ref "U2") (pin "15") (pinfunction "IN+2_15") (pintype "input"))
      (node (ref "U5") (pin "VOUT") (pinfunction "VOUT_VOUT") (pintype "power_in"))
    )
    (net (code "17") (name "G1") (class "Default")
      (node (ref "Q10") (pin "G") (pinfunction "G_G") (pintype "passive"))
      (node (ref "Q11") (pin "G") (pinfunction "G_G") (pintype "passive"))
      (node (ref "U5") (pin "G1") (pinfunction "G1_G1") (pintype "bidirectional"))
    )
    (net (code "18") (name "G2") (class "Default")
      (node (ref "Q12") (pin "G") (pinfunction "G_G") (pintype "passive"))
      (node (ref "Q13") (pin "G") (pinfunction "G_G") (pintype "passive"))
      (node (ref "U5") (pin "G2") (pinfunction "G2_G2") (pintype "bidirectional"))
    )
    (net (code "19") (name "GATE1") (class "Default")
      (node (ref "Q17") (pin "1") (pinfunction "G_1") (pintype "passive"))
      (node (ref "U6") (pin "5") (pinfunction "GATE_5") (pintype "passive"))
    )
    (net (code "20") (name "GATE2") (class "Default")
      (node (ref "Q18") (pin "1") (pinfunction "G_1") (pintype "passive"))
      (node (ref "U7") (pin "5") (pinfunction "GATE_5") (pintype "passive"))
    )
    (net (code "21") (name "GATE3") (class "Default")
      (node (ref "Q19") (pin "1") (pinfunction "G_1") (pintype "passive"))
      (node (ref "U8") (pin "5") (pinfunction "GATE_5") (pintype "passive"))
    )
    (net (code "22") (name "GATE4") (class "Default")
      (node (ref "Q20") (pin "1") (pinfunction "G_1") (pintype "passive"))
      (node (ref "U10") (pin "5") (pinfunction "GATE_5") (pintype "passive"))
    )
    (net (code "23") (name "GATE5") (class "Default")
      (node (ref "R46") (pin "1") (pinfunction "1_1") (pintype "passive"))
      (node (ref "U12") (pin "7") (pinfunction "HO_7") (pintype "bidirectional"))
    )
    (net (code "24") (name "GND") (class "Default")
      (node (ref "3V1") (pin "C") (pinfunction "C_C") (pintype "passive"))
      (node (ref "C1") (pin "2") (pinfunction "2_2") (pintype "passive"))
      (node (ref "C10") (pin "2") (pinfunction "2_2") (pintype "passive"))
      (node (ref "C13") (pin "2") (pinfunction "2_2") (pintype "passive"))
      (node (ref "C14") (pin "2") (pinfunction "2_2") (pintype "passive"))
      (node (ref "C15") (pin "2") (pinfunction "2_2") (pintype "passive"))
      (node (ref "C16") (pin "2") (pinfunction "2_2") (pintype "passive"))
      (node (ref "C17") (pin "2") (pinfunction "2_2") (pintype "passive"))
      (node (ref "C2") (pin "2") (pinfunction "2_2") (pintype "passive"))
      (node (ref "C3") (pin "2") (pinfunction "2_2") (pintype "passive"))
      (node (ref "C4") (pin "2") (pinfunction "2_2") (pintype "passive"))
      (node (ref "C5") (pin "2") (pinfunction "2_2") (pintype "passive"))
      (node (ref "C6") (pin "2") (pinfunction "2_2") (pintype "passive"))
      (node (ref "C7") (pin "2") (pinfunction "2_2") (pintype "passive"))
      (node (ref "C8") (pin "2") (pinfunction "2_2") (pintype "passive"))
      (node (ref "C9") (pin "2") (pinfunction "2_2") (pintype "passive"))
      (node (ref "CON1") (pin "2") (pinfunction "S_2") (pintype "passive"))
      (node (ref "CON2") (pin "P$4") (pinfunction "S_P$4") (pintype "passive"))
      (node (ref "CON2") (pin "P$5") (pinfunction "S_P$5") (pintype "passive"))
      (node (ref "CON3") (pin "P$4") (pinfunction "S_P$4") (pintype "passive"))
      (node (ref "CON3") (pin "P$5") (pinfunction "S_P$5") (pintype "passive"))
      (node (ref "DANGER1") (pin "C") (pinfunction "C_C") (pintype "passive"))
      (node (ref "J1") (pin "1") (pinfunction "KL_1") (pintype "passive"))
      (node (ref "J16") (pin "2") (pinfunction "KL1_2") (pintype "passive"))
      (node (ref "J9") (pin "1") (pinfunction "KL_1") (pintype "passive"))
      (node (ref "JP1") (pin "2") (pinfunction "2_2") (pintype "passive"))
      (node (ref "JP2") (pin "3") (pinfunction "3_3") (pintype "passive"))
      (node (ref "JP6") (pin "1") (pinfunction "1_1") (pintype "passive"))
      (node (ref "JP6") (pin "2") (pinfunction "2_2") (pintype "passive"))
      (node (ref "Q15") (pin "2D") (pinfunction "D_2D") (pintype "passive"))
      (node (ref "Q4") (pin "2D") (pinfunction "D_2D") (pintype "passive"))
      (node (ref "Q5") (pin "2D") (pinfunction "D_2D") (pintype "passive"))
      (node (ref "Q6") (pin "2D") (pinfunction "D_2D") (pintype "passive"))
      (node (ref "R18") (pin "1") (pinfunction "1_1") (pintype "passive"))
      (node (ref "R24") (pin "1") (pinfunction "1_1") (pintype "passive"))
      (node (ref "R27") (pin "1") (pinfunction "1_1") (pintype "passive"))
      (node (ref "R28") (pin "1") (pinfunction "1_1") (pintype "passive"))
      (node (ref "U1") (pin "3") (pinfunction "GND_3") (pintype "power_in"))
      (node (ref "U1") (pin "5") (pinfunction "A0_5") (pintype "input"))
      (node (ref "U10") (pin "2") (pinfunction "GND_2") (pintype "power_in"))
      (node (ref "U12") (pin "3") (pinfunction "LIN_3") (pintype "bidirectional"))
      (node (ref "U12") (pin "4") (pinfunction "GND_4") (pintype "bidirectional"))
      (node (ref "U2") (pin "3") (pinfunction "GND_3") (pintype "power_in"))
      (node (ref "U3") (pin "GND") (pinfunction "GND_GND") (pintype "power_in"))
      (node (ref "U4") (pin "2") (pinfunction "GND_2") (pintype "bidirectional"))
      (node (ref "U5") (pin "GND@1") (pinfunction "GND_GND@1") (pintype "power_in"))
      (node (ref "U5") (pin "GND@2") (pinfunction "GND_GND@2") (pintype "power_in"))
      (node (ref "U6") (pin "2") (pinfunction "GND_2") (pintype "power_in"))
      (node (ref "U7") (pin "2") (pinfunction "GND_2") (pintype "power_in"))
      (node (ref "U8") (pin "2") (pinfunction "GND_2") (pintype "power_in"))
    )
    (net (code "25") (name "HYS") (class "Default")
      (node (ref "R28") (pin "2") (pinfunction "2_2") (pintype "passive"))
      (node (ref "U5") (pin "HYS") (pinfunction "HYS_HYS") (pintype "bidirectional"))
    )
    (net (code "26") (name "IO1") (class "Default")
      (node (ref "U12") (pin "2") (pinfunction "HIN_2") (pintype "bidirectional"))
      (node (ref "U3") (pin "17/A3") (pinfunction "17/A3/T_17/A3") (pintype "bidirectional"))
    )
    (net (code "27") (name "IO2") (class "Default")
      (node (ref "U10") (pin "3") (pinfunction "OFF_3") (pintype "passive"))
      (node (ref "U3") (pin "13") (pinfunction "13/SCK/LED_13") (pintype "bidirectional"))
      (node (ref "U6") (pin "3") (pinfunction "OFF_3") (pintype "passive"))
      (node (ref "U7") (pin "3") (pinfunction "OFF_3") (pintype "passive"))
      (node (ref "U8") (pin "3") (pinfunction "OFF_3") (pintype "passive"))
    )
    (net (code "28") (name "IO3") (class "Default")
      (node (ref "R42") (pin "1") (pinfunction "1_1") (pintype "passive"))
      (node (ref "U3") (pin "15/A1") (pinfunction "15/A1/T_15/A1") (pintype "bidirectional"))
      (node (ref "U7") (pin "1") (pinfunction "NFGD_1") (pintype "passive"))
    )
    (net (code "29") (name "IO4") (class "Default")
      (node (ref "R41") (pin "1") (pinfunction "1_1") (pintype "passive"))
      (node (ref "U3") (pin "12") (pinfunction "12/MISO_12") (pintype "bidirectional"))
      (node (ref "U8") (pin "1") (pinfunction "NFGD_1") (pintype "passive"))
    )
    (net (code "30") (name "IO5") (class "Default")
      (node (ref "R43") (pin "1") (pinfunction "1_1") (pintype "passive"))
      (node (ref "U3") (pin "16/A2") (pinfunction "16/A2/T_16/A2") (pintype "bidirectional"))
      (node (ref "U6") (pin "1") (pinfunction "NFGD_1") (pintype "passive"))
    )
    (net (code "31") (name "IO6") (class "Default")
      (node (ref "R44") (pin "1") (pinfunction "1_1") (pintype "passive"))
      (node (ref "U10") (pin "1") (pinfunction "NFGD_1") (pintype "passive"))
      (node (ref "U3") (pin "14/A0") (pinfunction "14/A0_14/A0") (pintype "bidirectional"))
    )
    (net (code "32") (name "LED_D") (class "Default")
      (node (ref "R36") (pin "1") (pinfunction "1_1") (pintype "passive"))
      (node (ref "U3") (pin "23/A9") (pinfunction "23/A9/T/PWM_23/A9") (pintype "bidirectional"))
    )
    (net (code "33") (name "MOTOR1") (class "Default")
      (node (ref "C14") (pin "1") (pinfunction "1_1") (pintype "passive"))
      (node (ref "Q17") (pin "3") (pinfunction "S_3") (pintype "passive"))
      (node (ref "R8") (pin "P$1") (pinfunction "1_P$1") (pintype "passive"))
      (node (ref "U1") (pin "11") (pinfunction "IN-1_11") (pintype "input"))
      (node (ref "U6") (pin "4") (pinfunction "IN_4") (pintype "input"))
    )
    (net (code "34") (name "MOTOR2") (class "Default")
      (node (ref "C13") (pin "1") (pinfunction "1_1") (pintype "passive"))
      (node (ref "Q18") (pin "3") (pinfunction "S_3") (pintype "passive"))
      (node (ref "R4") (pin "P$1") (pinfunction "1_P$1") (pintype "passive"))
      (node (ref "U1") (pin "14") (pinfunction "IN-2_14") (pintype "input"))
      (node (ref "U7") (pin "4") (pinfunction "IN_4") (pintype "input"))
    )
    (net (code "35") (name "MOTOR3") (class "Default")
      (node (ref "C15") (pin "1") (pinfunction "1_1") (pintype "passive"))
      (node (ref "Q19") (pin "3") (pinfunction "S_3") (pintype "passive"))
      (node (ref "R13") (pin "P$1") (pinfunction "1_P$1") (pintype "passive"))
      (node (ref "U2") (pin "11") (pinfunction "IN-1_11") (pintype "input"))
      (node (ref "U8") (pin "4") (pinfunction "IN_4") (pintype "input"))
    )
    (net (code "36") (name "MOTOR4") (class "Default")
      (node (ref "C16") (pin "1") (pinfunction "1_1") (pintype "passive"))
      (node (ref "Q20") (pin "3") (pinfunction "S_3") (pintype "passive"))
      (node (ref "R35") (pin "P$1") (pinfunction "1_P$1") (pintype "passive"))
      (node (ref "U1") (pin "1") (pinfunction "IN-3_1") (pintype "input"))
      (node (ref "U10") (pin "4") (pinfunction "IN_4") (pintype "input"))
    )
    (net (code "37") (name "NIU") (class "Default")
      (node (ref "C6") (pin "1") (pinfunction "1_1") (pintype "passive"))
      (node (ref "U5") (pin "!SHDN") (pinfunction "~{SHDN}_!SHDN") (pintype "bidirectional"))
      (node (ref "U5") (pin "EN") (pinfunction "EN_EN") (pintype "bidirectional"))
      (node (ref "U5") (pin "INTVCC") (pinfunction "INTVCC_INTVCC") (pintype "bidirectional"))
    )
    (net (code "38") (name "Net-(3V1-PadA)") (class "Default")
      (node (ref "3V1") (pin "A") (pinfunction "A_A") (pintype "passive"))
      (node (ref "R37") (pin "1") (pinfunction "1_1") (pintype "passive"))
    )
    (net (code "39") (name "Net-(C5-Pad1)") (class "Default")
      (node (ref "C5") (pin "1") (pinfunction "1_1") (pintype "passive"))
      (node (ref "U5") (pin "TMR") (pinfunction "TMR_TMR") (pintype "bidirectional"))
    )
    (net (code "40") (name "Net-(CON2A-S)") (class "Default")
      (node (ref "CON2") (pin "P$1") (pinfunction "S_P$1") (pintype "passive"))
      (node (ref "CON3") (pin "P$1") (pinfunction "S_P$1") (pintype "passive"))
    )
    (net (code "41") (name "Net-(CON2B-S)") (class "Default")
      (node (ref "CON2") (pin "P$2") (pinfunction "S_P$2") (pintype "passive"))
      (node (ref "CON3") (pin "P$2") (pinfunction "S_P$2") (pintype "passive"))
      (node (ref "U4") (pin "6") (pinfunction "CANL_6") (pintype "bidirectional"))
    )
    (net (code "42") (name "Net-(CON2C-S)") (class "Default")
      (node (ref "CON2") (pin "P$3") (pinfunction "S_P$3") (pintype "passive"))
      (node (ref "CON3") (pin "P$3") (pinfunction "S_P$3") (pintype "passive"))
      (node (ref "U4") (pin "7") (pinfunction "CANH_7") (pintype "bidirectional"))
    )
    (net (code "43") (name "Net-(D1-A)") (class "Default")
      (node (ref "D1") (pin "P$2") (pinfunction "A_P$2") (pintype "passive"))
      (node (ref "J4") (pin "1") (pinfunction "KL_1") (pintype "passive"))
      (node (ref "Q4") (pin "3S") (pinfunction "S_3S") (pintype "passive"))
      (node (ref "R21") (pin "1") (pinfunction "1_1") (pintype "passive"))
      (node (ref "R9") (pin "1") (pinfunction "1_1") (pintype "passive"))
    )
    (net (code "44") (name "Net-(D1-C)") (class "Default")
      (node (ref "D1") (pin "P$1") (pinfunction "C_P$1") (pintype "passive"))
      (node (ref "Q4") (pin "1G") (pinfunction "G_1G") (pintype "passive"))
      (node (ref "R5") (pin "1") (pinfunction "1_1") (pintype "passive"))
      (node (ref "R9") (pin "2") (pinfunction "2_2") (pintype "passive"))
    )
    (net (code "45") (name "Net-(D2-A)") (class "Default")
      (node (ref "D2") (pin "P$2") (pinfunction "A_P$2") (pintype "passive"))
      (node (ref "J3") (pin "1") (pinfunction "KL_1") (pintype "passive"))
      (node (ref "Q5") (pin "3S") (pinfunction "S_3S") (pintype "passive"))
      (node (ref "R10") (pin "1") (pinfunction "1_1") (pintype "passive"))
      (node (ref "R19") (pin "1") (pinfunction "1_1") (pintype "passive"))
    )
    (net (code "46") (name "Net-(D2-C)") (class "Default")
      (node (ref "D2") (pin "P$1") (pinfunction "C_P$1") (pintype "passive"))
      (node (ref "Q5") (pin "1G") (pinfunction "G_1G") (pintype "passive"))
      (node (ref "R10") (pin "2") (pinfunction "2_2") (pintype "passive"))
      (node (ref "R6") (pin "1") (pinfunction "1_1") (pintype "passive"))
    )
    (net (code "47") (name "Net-(D3-A)") (class "Default")
      (node (ref "D3") (pin "P$2") (pinfunction "A_P$2") (pintype "passive"))
      (node (ref "J2") (pin "1") (pinfunction "KL_1") (pintype "passive"))
      (node (ref "Q6") (pin "3S") (pinfunction "S_3S") (pintype "passive"))
      (node (ref "R11") (pin "1") (pinfunction "1_1") (pintype "passive"))
      (node (ref "R20") (pin "1") (pinfunction "1_1") (pintype "passive"))
    )
    (net (code "48") (name "Net-(D3-C)") (class "Default")
      (node (ref "D3") (pin "P$1") (pinfunction "C_P$1") (pintype "passive"))
      (node (ref "Q6") (pin "1G") (pinfunction "G_1G") (pintype "passive"))
      (node (ref "R11") (pin "2") (pinfunction "2_2") (pintype "passive"))
      (node (ref "R7") (pin "1") (pinfunction "1_1") (pintype "passive"))
    )
    (net (code "49") (name "Net-(D4-A)") (class "Default")
      (node (ref "D4") (pin "P$2") (pinfunction "A_P$2") (pintype "passive"))
      (node (ref "J10") (pin "1") (pinfunction "KL_1") (pintype "passive"))
      (node (ref "Q15") (pin "3S") (pinfunction "S_3S") (pintype "passive"))
      (node (ref "R31") (pin "1") (pinfunction "1_1") (pintype "passive"))
      (node (ref "R32") (pin "1") (pinfunction "1_1") (pintype "passive"))
    )
    (net (code "50") (name "Net-(D4-C)") (class "Default")
      (node (ref "D4") (pin "P$1") (pinfunction "C_P$1") (pintype "passive"))
      (node (ref "Q15") (pin "1G") (pinfunction "G_1G") (pintype "passive"))
      (node (ref "R32") (pin "2") (pinfunction "2_2") (pintype "passive"))
      (node (ref "R33") (pin "1") (pinfunction "1_1") (pintype "passive"))
    )
    (net (code "51") (name "Net-(D5-PadA)") (class "Default")
      (node (ref "D5") (pin "A") (pinfunction "A_A") (pintype "passive"))
      (node (ref "R45") (pin "2") (pinfunction "2_2") (pintype "passive"))
    )
    (net (code "52") (name "Net-(DANGER1-PadA)") (class "Default")
      (node (ref "DANGER1") (pin "A") (pinfunction "A_A") (pintype "passive"))
      (node (ref "R36") (pin "2") (pinfunction "2_2") (pintype "passive"))
    )
    (net (code "53") (name "Net-(JP2-Pad2)") (class "Default")
      (node (ref "JP2") (pin "2") (pinfunction "2_2") (pintype "passive"))
      (node (ref "JP3") (pin "2") (pinfunction "2_2") (pintype "passive"))
    )
    (net (code "54") (name "Net-(JP5-Pad2)") (class "Default")
      (node (ref "JP5") (pin "2") (pinfunction "2_2") (pintype "passive"))
      (node (ref "R14") (pin "1") (pinfunction "1_1") (pintype "passive"))
    )
    (net (code "55") (name "Net-(JP5-Pad4)") (class "Default")
      (node (ref "JP5") (pin "4") (pinfunction "4_4") (pintype "passive"))
      (node (ref "R15") (pin "1") (pinfunction "1_1") (pintype "passive"))
    )
    (net (code "56") (name "Net-(JP5-Pad6)") (class "Default")
      (node (ref "JP5") (pin "6") (pinfunction "6_6") (pintype "passive"))
      (node (ref "JP6") (pin "7") (pinfunction "7_7") (pintype "passive"))
      (node (ref "JP6") (pin "8") (pinfunction "8_8") (pintype "passive"))
    )
    (net (code "57") (name "Net-(LED1-PadA)") (class "Default")
      (node (ref "LED1") (pin "A") (pinfunction "A_A") (pintype "passive"))
      (node (ref "R29") (pin "1") (pinfunction "1_1") (pintype "passive"))
    )
    (net (code "58") (name "Net-(LED2-PadA)") (class "Default")
      (node (ref "LED2") (pin "A") (pinfunction "A_A") (pintype "passive"))
      (node (ref "R30") (pin "1") (pinfunction "1_1") (pintype "passive"))
    )
    (net (code "59") (name "Net-(Q1-A)") (class "Default")
      (node (ref "Q1") (pin "P$1") (pinfunction "A_P$1") (pintype "bidirectional"))
      (node (ref "R1") (pin "2") (pinfunction "2_2") (pintype "passive"))
    )
    (net (code "60") (name "Net-(Q1-C1)") (class "Default")
      (node (ref "JP1") (pin "1") (pinfunction "1_1") (pintype "passive"))
      (node (ref "JP3") (pin "1") (pinfunction "1_1") (pintype "passive"))
      (node (ref "Q1") (pin "P$2") (pinfunction "C1_P$2") (pintype "bidirectional"))
      (node (ref "Q16") (pin "P$2") (pinfunction "C1_P$2") (pintype "bidirectional"))
      (node (ref "Q2") (pin "P$2") (pinfunction "C1_P$2") (pintype "bidirectional"))
      (node (ref "Q3") (pin "P$2") (pinfunction "C1_P$2") (pintype "bidirectional"))
    )
    (net (code "61") (name "Net-(Q1-E)") (class "Default")
      (node (ref "Q1") (pin "P$3") (pinfunction "E_P$3") (pintype "bidirectional"))
      (node (ref "R5") (pin "2") (pinfunction "2_2") (pintype "passive"))
    )
    (net (code "62") (name "Net-(Q2-A)") (class "Default")
      (node (ref "Q2") (pin "P$1") (pinfunction "A_P$1") (pintype "bidirectional"))
      (node (ref "R2") (pin "2") (pinfunction "2_2") (pintype "passive"))
    )
    (net (code "63") (name "Net-(Q2-E)") (class "Default")
      (node (ref "Q2") (pin "P$3") (pinfunction "E_P$3") (pintype "bidirectional"))
      (node (ref "R6") (pin "2") (pinfunction "2_2") (pintype "passive"))
    )
    (net (code "64") (name "Net-(Q3-A)") (class "Default")
      (node (ref "Q3") (pin "P$1") (pinfunction "A_P$1") (pintype "bidirectional"))
      (node (ref "R3") (pin "2") (pinfunction "2_2") (pintype "passive"))
    )
    (net (code "65") (name "Net-(Q3-E)") (class "Default")
      (node (ref "Q3") (pin "P$3") (pinfunction "E_P$3") (pintype "bidirectional"))
      (node (ref "R7") (pin "2") (pinfunction "2_2") (pintype "passive"))
    )
    (net (code "66") (name "Net-(Q7-PadG)") (class "Default")
      (node (ref "Q7") (pin "G") (pinfunction "G_G") (pintype "passive"))
      (node (ref "R19") (pin "2") (pinfunction "2_2") (pintype "passive"))
    )
    (net (code "67") (name "Net-(Q8-PadG)") (class "Default")
      (node (ref "Q8") (pin "G") (pinfunction "G_G") (pintype "passive"))
      (node (ref "R31") (pin "2") (pinfunction "2_2") (pintype "passive"))
    )
    (net (code "68") (name "Net-(Q9-PadG)") (class "Default")
      (node (ref "Q9") (pin "G") (pinfunction "G_G") (pintype "passive"))
      (node (ref "R21") (pin "2") (pinfunction "2_2") (pintype "passive"))
    )
    (net (code "69") (name "Net-(Q14-PadG)") (class "Default")
      (node (ref "Q14") (pin "G") (pinfunction "G_G") (pintype "passive"))
      (node (ref "R20") (pin "2") (pinfunction "2_2") (pintype "passive"))
    )
    (net (code "70") (name "Net-(Q16-A)") (class "Default")
      (node (ref "Q16") (pin "P$1") (pinfunction "A_P$1") (pintype "bidirectional"))
      (node (ref "R34") (pin "2") (pinfunction "2_2") (pintype "passive"))
    )
    (net (code "71") (name "Net-(Q16-E)") (class "Default")
      (node (ref "Q16") (pin "P$3") (pinfunction "E_P$3") (pintype "bidirectional"))
      (node (ref "R33") (pin "2") (pinfunction "2_2") (pintype "passive"))
    )
    (net (code "72") (name "Net-(Q21-G)") (class "Default")
      (node (ref "Q21") (pin "4") (pinfunction "G_4") (pintype "passive"))
      (node (ref "R46") (pin "2") (pinfunction "2_2") (pintype "passive"))
    )
    (net (code "73") (name "Net-(U4-RXD)") (class "Default")
      (node (ref "R17") (pin "2") (pinfunction "2_2") (pintype "passive"))
      (node (ref "U4") (pin "4") (pinfunction "RXD_4") (pintype "bidirectional"))
    )
    (net (code "74") (name "Net-(U4-STB)") (class "Default")
      (node (ref "R18") (pin "2") (pinfunction "2_2") (pintype "passive"))
      (node (ref "U4") (pin "8") (pinfunction "STB_8") (pintype "bidirectional"))
    )
    (net (code "75") (name "Net-(U4-TXD)") (class "Default")
      (node (ref "R16") (pin "2") (pinfunction "2_2") (pintype "passive"))
      (node (ref "U4") (pin "1") (pinfunction "TXD_1") (pintype "bidirectional"))
    )
    (net (code "76") (name "Net-(U5-~{VALID1})") (class "Default")
      (node (ref "LED2") (pin "C") (pinfunction "C_C") (pintype "passive"))
      (node (ref "U5") (pin "!VALID1") (pinfunction "~{VALID1}_!VALID1") (pintype "bidirectional"))
    )
    (net (code "77") (name "Net-(U5-~{VALID2})") (class "Default")
      (node (ref "LED1") (pin "C") (pinfunction "C_C") (pintype "passive"))
      (node (ref "U5") (pin "!VALID2") (pinfunction "~{VALID2}_!VALID2") (pintype "bidirectional"))
    )
    (net (code "78") (name "Net-(U12-VB)") (class "Default")
      (node (ref "C18") (pin "1") (pinfunction "1_1") (pintype "passive"))
      (node (ref "D5") (pin "C") (pinfunction "C_C") (pintype "passive"))
      (node (ref "U12") (pin "8") (pinfunction "VB_8") (pintype "bidirectional"))
    )
    (net (code "79") (name "Net-(U12-VS)") (class "Default")
      (node (ref "C18") (pin "2") (pinfunction "2_2") (pintype "passive"))
      (node (ref "U12") (pin "6") (pinfunction "VS_6") (pintype "bidirectional"))
    )
    (net (code "80") (name "OV1") (class "Default")
      (node (ref "R23") (pin "1") (pinfunction "1_1") (pintype "passive"))
      (node (ref "R24") (pin "2") (pinfunction "2_2") (pintype "passive"))
      (node (ref "U5") (pin "OV1") (pinfunction "OV1_OV1") (pintype "bidirectional"))
    )
    (net (code "81") (name "OV2") (class "Default")
      (node (ref "R26") (pin "1") (pinfunction "1_1") (pintype "passive"))
      (node (ref "R27") (pin "2") (pinfunction "2_2") (pintype "passive"))
      (node (ref "U5") (pin "OV2") (pinfunction "OV2_OV2") (pintype "bidirectional"))
    )
    (net (code "82") (name "POWER_BOARD") (class "Default")
      (node (ref "C17") (pin "1") (pinfunction "1_1") (pintype "passive"))
      (node (ref "Q21") (pin "5") (pinfunction "D_5") (pintype "passive"))
      (node (ref "Q21") (pin "6") (pinfunction "D_6") (pintype "passive"))
      (node (ref "Q21") (pin "7") (pinfunction "D_7") (pintype "passive"))
      (node (ref "Q21") (pin "8") (pinfunction "D_8") (pintype "passive"))
      (node (ref "R12") (pin "P$1") (pinfunction "1_P$1") (pintype "passive"))
      (node (ref "R45") (pin "1") (pinfunction "1_1") (pintype "passive"))
      (node (ref "U12") (pin "1") (pinfunction "VCC_1") (pintype "bidirectional"))
      (node (ref "U2") (pin "1") (pinfunction "IN-3_1") (pintype "input"))
      (node (ref "U2") (pin "14") (pinfunction "IN-2_14") (pintype "input"))
    )
    (net (code "83") (name "PV_OUT") (class "Default")
      (node (ref "U1") (pin "10") (pinfunction "PV_10") (pintype "output"))
      (node (ref "U2") (pin "10") (pinfunction "PV_10") (pintype "output"))
      (node (ref "U3") (pin "7") (pinfunction "7/RX3_7") (pintype "bidirectional"))
    )
    (net (code "84") (name "SCL") (class "Default")
      (node (ref "JP6") (pin "5") (pinfunction "5_5") (pintype "passive"))
      (node (ref "JP6") (pin "6") (pinfunction "6_6") (pintype "passive"))
      (node (ref "R14") (pin "2") (pinfunction "2_2") (pintype "passive"))
      (node (ref "U1") (pin "6") (pinfunction "SCL_6") (pintype "input"))
      (node (ref "U2") (pin "6") (pinfunction "SCL_6") (pintype "input"))
      (node (ref "U3") (pin "19/A5") (pinfunction "19/A5/T/SCL0_19/A5") (pintype "bidirectional"))
    )
    (net (code "85") (name "SDA") (class "Default")
      (node (ref "JP6") (pin "3") (pinfunction "3_3") (pintype "passive"))
      (node (ref "JP6") (pin "4") (pinfunction "4_4") (pintype "passive"))
      (node (ref "R15") (pin "2") (pinfunction "2_2") (pintype "passive"))
      (node (ref "U1") (pin "7") (pinfunction "SDA_7") (pintype "bidirectional"))
      (node (ref "U2") (pin "7") (pinfunction "SDA_7") (pintype "bidirectional"))
      (node (ref "U3") (pin "18/A4") (pinfunction "18/A4/T/SDA0_18/A4") (pintype "bidirectional"))
    )
    (net (code "86") (name "TC_OUT") (class "Default")
      (node (ref "U1") (pin "13") (pinfunction "TC_13") (pintype "output"))
      (node (ref "U2") (pin "13") (pinfunction "TC_13") (pintype "output"))
      (node (ref "U3") (pin "8") (pinfunction "8/TX3_8") (pintype "bidirectional"))
    )
    (net (code "87") (name "UV1") (class "Default")
      (node (ref "R22") (pin "1") (pinfunction "1_1") (pintype "passive"))
      (node (ref "R23") (pin "2") (pinfunction "2_2") (pintype "passive"))
      (node (ref "U5") (pin "UV1") (pinfunction "UV1_UV1") (pintype "bidirectional"))
    )
    (net (code "88") (name "UV2") (class "Default")
      (node (ref "R25") (pin "1") (pinfunction "1_1") (pintype "passive"))
      (node (ref "R26") (pin "2") (pinfunction "2_2") (pintype "passive"))
      (node (ref "U5") (pin "UV2") (pinfunction "UV2_UV2") (pintype "bidirectional"))
    )
    (net (code "89") (name "VIN") (class "Default")
      (node (ref "C4") (pin "1") (pinfunction "1_1") (pintype "passive"))
      (node (ref "JP4") (pin "1") (pinfunction "1_1") (pintype "passive"))
      (node (ref "U3") (pin "VIN") (pinfunction "VIN_VIN") (pintype "power_in"))
      (node (ref "U4") (pin "3") (pinfunction "VCC_3") (pintype "bidirectional"))
    )
    (net (code "90") (name "VOUT") (class "Default")
      (node (ref "J16") (pin "1") (pinfunction "KL_1") (pintype "passive"))
      (node (ref "Q17") (pin "2") (pinfunction "D_2") (pintype "passive"))
      (node (ref "Q18") (pin "2") (pinfunction "D_2") (pintype "passive"))
      (node (ref "Q19") (pin "2") (pinfunction "D_2") (pintype "passive"))
      (node (ref "Q20") (pin "2") (pinfunction "D_2") (pintype "passive"))
      (node (ref "Q21") (pin "1") (pinfunction "S_1") (pintype "passive"))
      (node (ref "Q21") (pin "2") (pinfunction "S_2") (pintype "passive"))
      (node (ref "Q21") (pin "3") (pinfunction "S_3") (pintype "passive"))
      (node (ref "U10") (pin "6") (pinfunction "OUT_6") (pintype "output"))
      (node (ref "U6") (pin "6") (pinfunction "OUT_6") (pintype "output"))
      (node (ref "U7") (pin "6") (pinfunction "OUT_6") (pintype "output"))
      (node (ref "U8") (pin "6") (pinfunction "OUT_6") (pintype "output"))
    )
    (net (code "91") (name "VS1") (class "Default")
      (node (ref "C9") (pin "1") (pinfunction "1_1") (pintype "passive"))
      (node (ref "Q10") (pin "S@1") (pinfunction "S_S@1") (pintype "passive"))
      (node (ref "Q10") (pin "S@2") (pinfunction "S_S@2") (pintype "passive"))
      (node (ref "Q10") (pin "S@3") (pinfunction "S_S@3") (pintype "passive"))
      (node (ref "Q11") (pin "S@1") (pinfunction "S_S@1") (pintype "passive"))
      (node (ref "Q11") (pin "S@2") (pinfunction "S_S@2") (pintype "passive"))
      (node (ref "Q11") (pin "S@3") (pinfunction "S_S@3") (pintype "passive"))
      (node (ref "U5") (pin "VS1") (pinfunction "VS1_VS1") (pintype "bidirectional"))
    )
    (net (code "92") (name "VS2") (class "Default")
      (node (ref "C10") (pin "1") (pinfunction "1_1") (pintype "passive"))
      (node (ref "Q12") (pin "S@1") (pinfunction "S_S@1") (pintype "passive"))
      (node (ref "Q12") (pin "S@2") (pinfunction "S_S@2") (pintype "passive"))
      (node (ref "Q12") (pin "S@3") (pinfunction "S_S@3") (pintype "passive"))
      (node (ref "Q13") (pin "S@1") (pinfunction "S_S@1") (pintype "passive"))
      (node (ref "Q13") (pin "S@2") (pinfunction "S_S@2") (pintype "passive"))
      (node (ref "Q13") (pin "S@3") (pinfunction "S_S@3") (pintype "passive"))
      (node (ref "U5") (pin "VS2") (pinfunction "VS2_VS2") (pintype "bidirectional"))
    )
    (net (code "93") (name "WALL") (class "Default")
      (node (ref "C7") (pin "1") (pinfunction "1_1") (pintype "passive"))
      (node (ref "J9") (pin "2") (pinfunction "KL1_2") (pintype "passive"))
      (node (ref "Q10") (pin "D@1") (pinfunction "D_D@1") (pintype "passive"))
      (node (ref "Q10") (pin "D@2") (pinfunction "D_D@2") (pintype "passive"))
      (node (ref "Q10") (pin "D@3") (pinfunction "D_D@3") (pintype "passive"))
      (node (ref "Q10") (pin "D@4") (pinfunction "D_D@4") (pintype "passive"))
      (node (ref "Q10") (pin "D@5") (pinfunction "D_D@5") (pintype "passive"))
      (node (ref "R22") (pin "2") (pinfunction "2_2") (pintype "passive"))
      (node (ref "U5") (pin "V1") (pinfunction "V1_V1") (pintype "bidirectional"))
    )
    (net (code "94") (name "WARNING_OUT") (class "Default")
      (node (ref "U1") (pin "8") (pinfunction "WARNING_8") (pintype "output"))
      (node (ref "U2") (pin "8") (pinfunction "WARNING_8") (pintype "output"))
      (node (ref "U3") (pin "10") (pinfunction "10/TX2/PWM_10") (pintype "bidirectional"))
    )
    (net (code "95") (name "unconnected-(U2-IN+3-Pad2)") (class "Default")
      (node (ref "U2") (pin "2") (pinfunction "IN+3_2") (pintype "input"))
    )
    (net (code "96") (name "unconnected-(U3-0{slash}RX1{slash}T-Pad0)") (class "Default")
      (node (ref "U3") (pin "0") (pinfunction "0/RX1/T_0") (pintype "bidirectional"))
    )
    (net (code "97") (name "unconnected-(U3-1{slash}TX1{slash}T-Pad1)") (class "Default")
      (node (ref "U3") (pin "1") (pinfunction "1/TX1/T_1") (pintype "bidirectional"))
    )
    (net (code "98") (name "unconnected-(U3-5{slash}PWM-Pad5)") (class "Default")
      (node (ref "U3") (pin "5") (pinfunction "5/PWM_5") (pintype "bidirectional"))
    )
    (net (code "99") (name "unconnected-(U3-6{slash}PWM-Pad6)") (class "Default")
      (node (ref "U3") (pin "6") (pinfunction "6/PWM_6") (pintype "bidirectional"))
    )
    (net (code "100") (name "unconnected-(U3-11{slash}MOSI-Pad11)") (class "Default")
      (node (ref "U3") (pin "11") (pinfunction "11/MOSI_11") (pintype "bidirectional"))
    )
    (net (code "101") (name "unconnected-(U3-20{slash}A6{slash}PWM-Pad20{slash}A6)") (class "Default")
      (node (ref "U3") (pin "20/A6") (pinfunction "20/A6/PWM_20/A6") (pintype "bidirectional"))
    )
    (net (code "102") (name "unconnected-(U3-21{slash}A7{slash}PWM-Pad21{slash}A7)") (class "Default")
      (node (ref "U3") (pin "21/A7") (pinfunction "21/A7/PWM_21/A7") (pintype "bidirectional"))
    )
    (net (code "103") (name "unconnected-(U3-22{slash}A8{slash}T{slash}PWM-Pad22{slash}A8)") (class "Default")
      (node (ref "U3") (pin "22/A8") (pinfunction "22/A8/T/PWM_22/A8") (pintype "bidirectional"))
    )
    (net (code "104") (name "unconnected-(U3-Pad2)") (class "Default")
      (node (ref "U3") (pin "2") (pinfunction "2_2") (pintype "bidirectional"))
    )
    (net (code "105") (name "unconnected-(U5-PadCAS)") (class "Default")
      (node (ref "U5") (pin "CAS") (pinfunction "CAS_CAS") (pintype "bidirectional"))
    )
    (net (code "106") (name "unconnected-(U12-LO-Pad5)") (class "Default")
      (node (ref "U12") (pin "5") (pinfunction "LO_5") (pintype "bidirectional"))
    )
  )
)
